# Grove_Beginner_Kit_for_Arduino.net
KiCad netlist of a schematic drawn in EAGLE
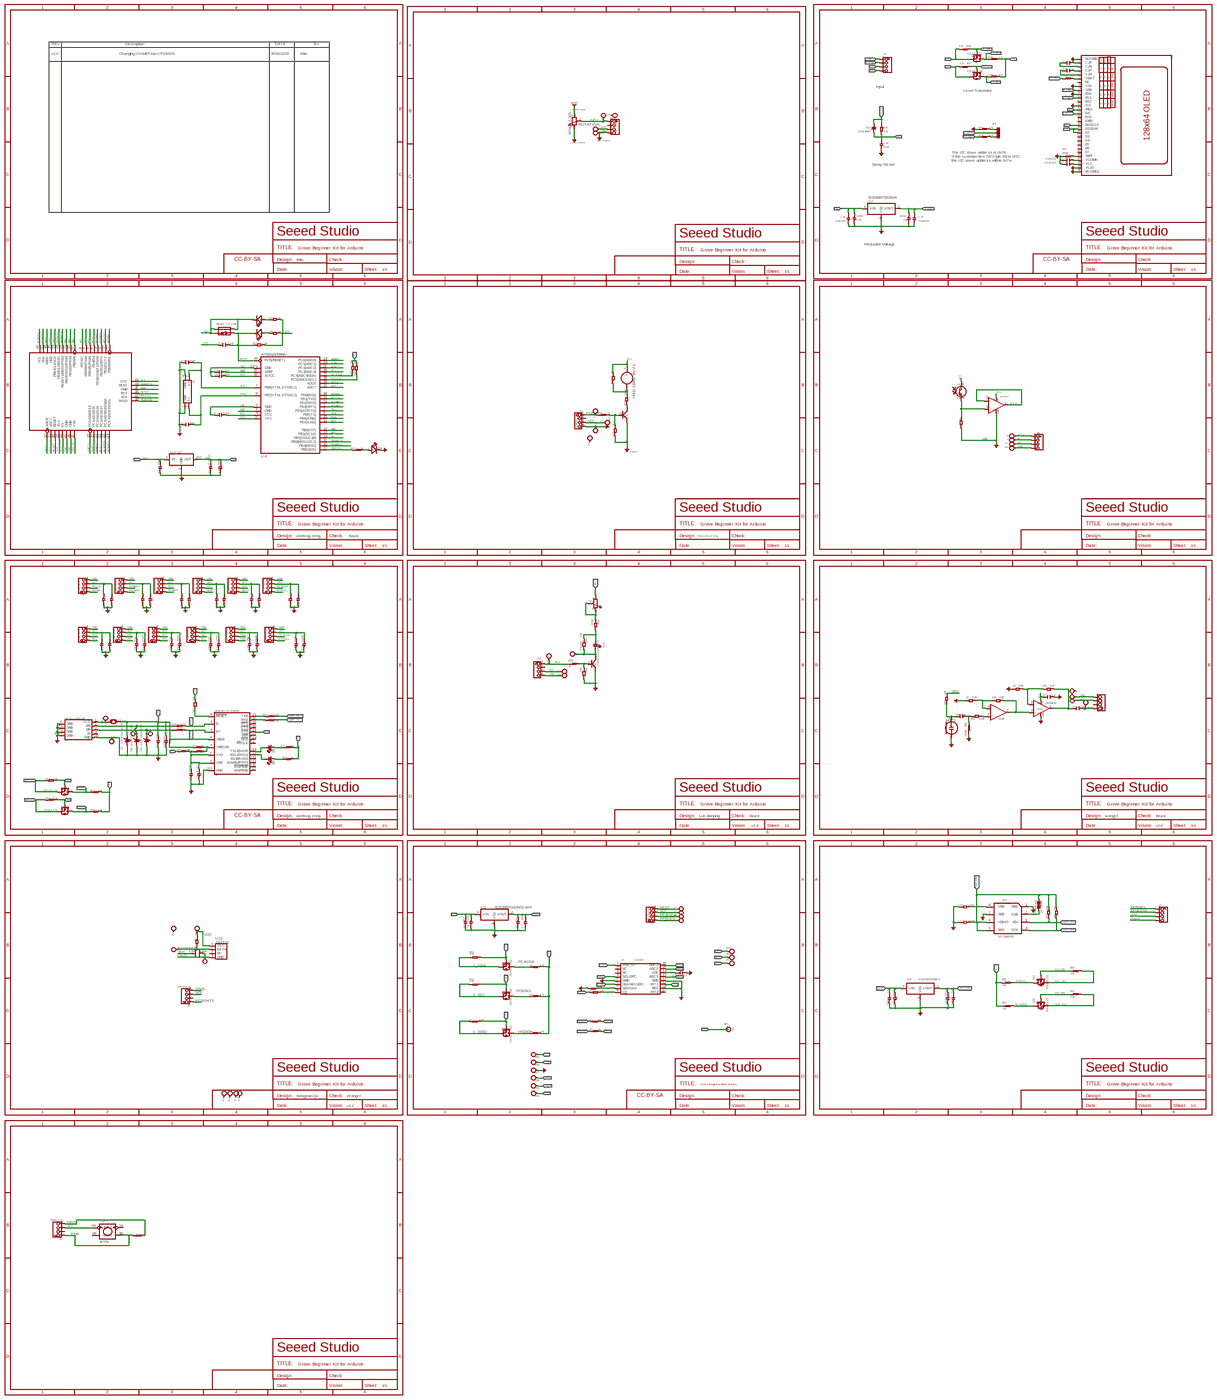
[diagram p0: schematic, sheet 1, overview]
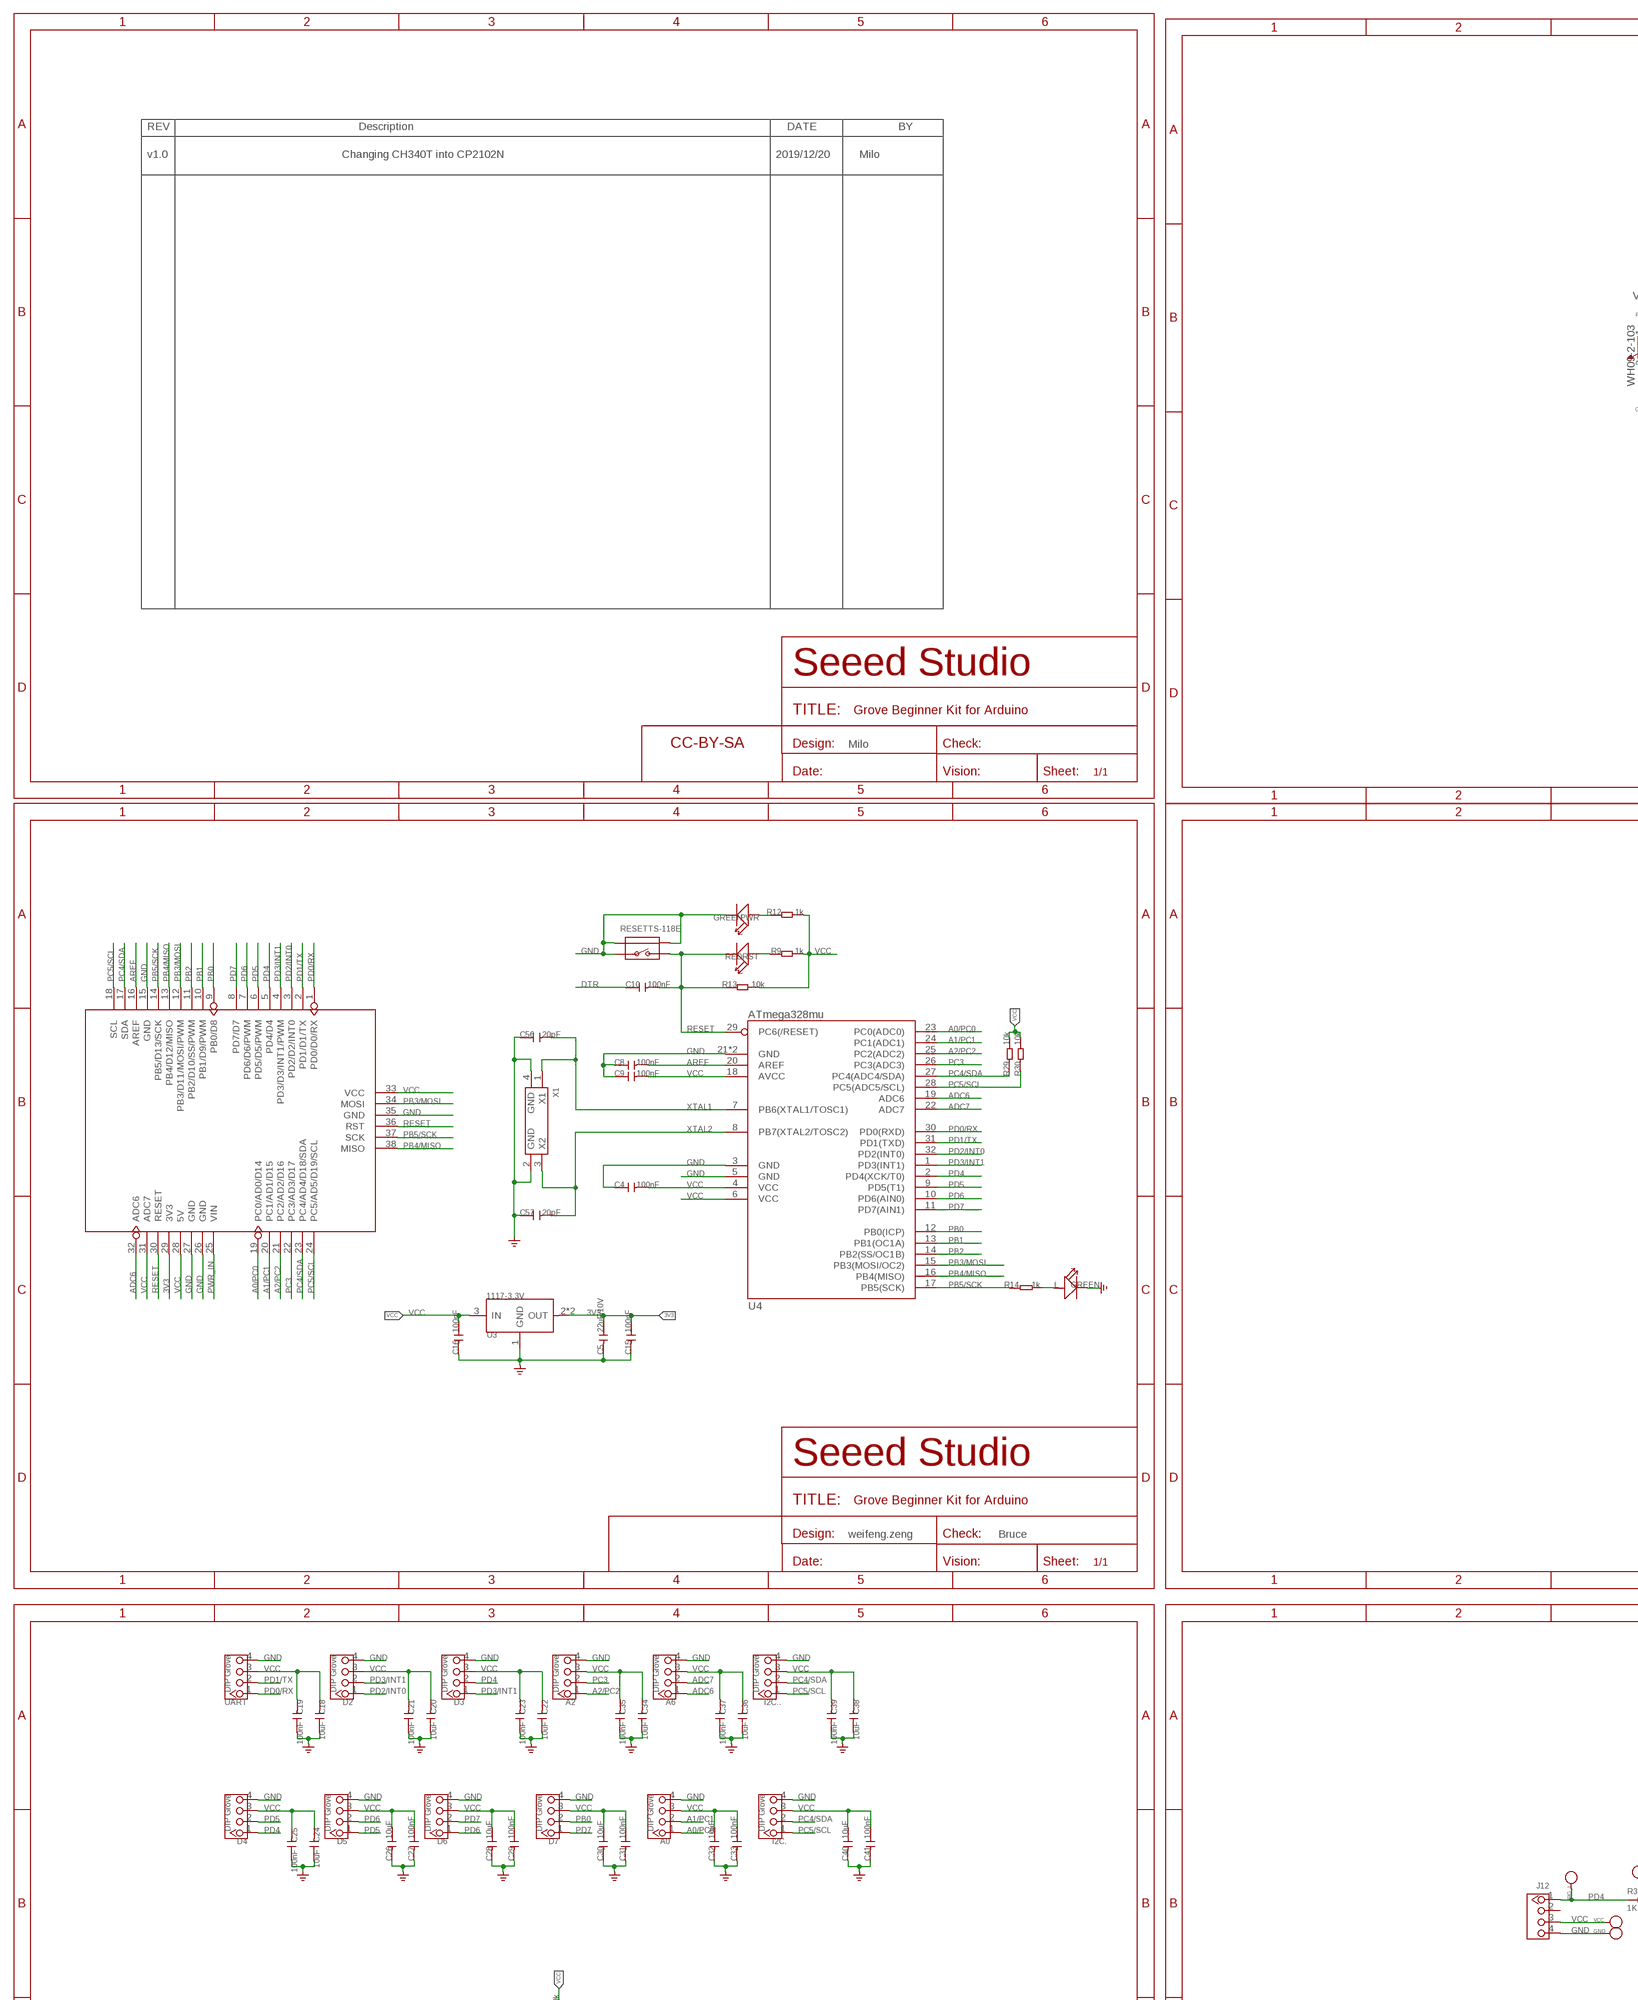
[diagram p1: schematic, sheet 1, part 1 of 4]
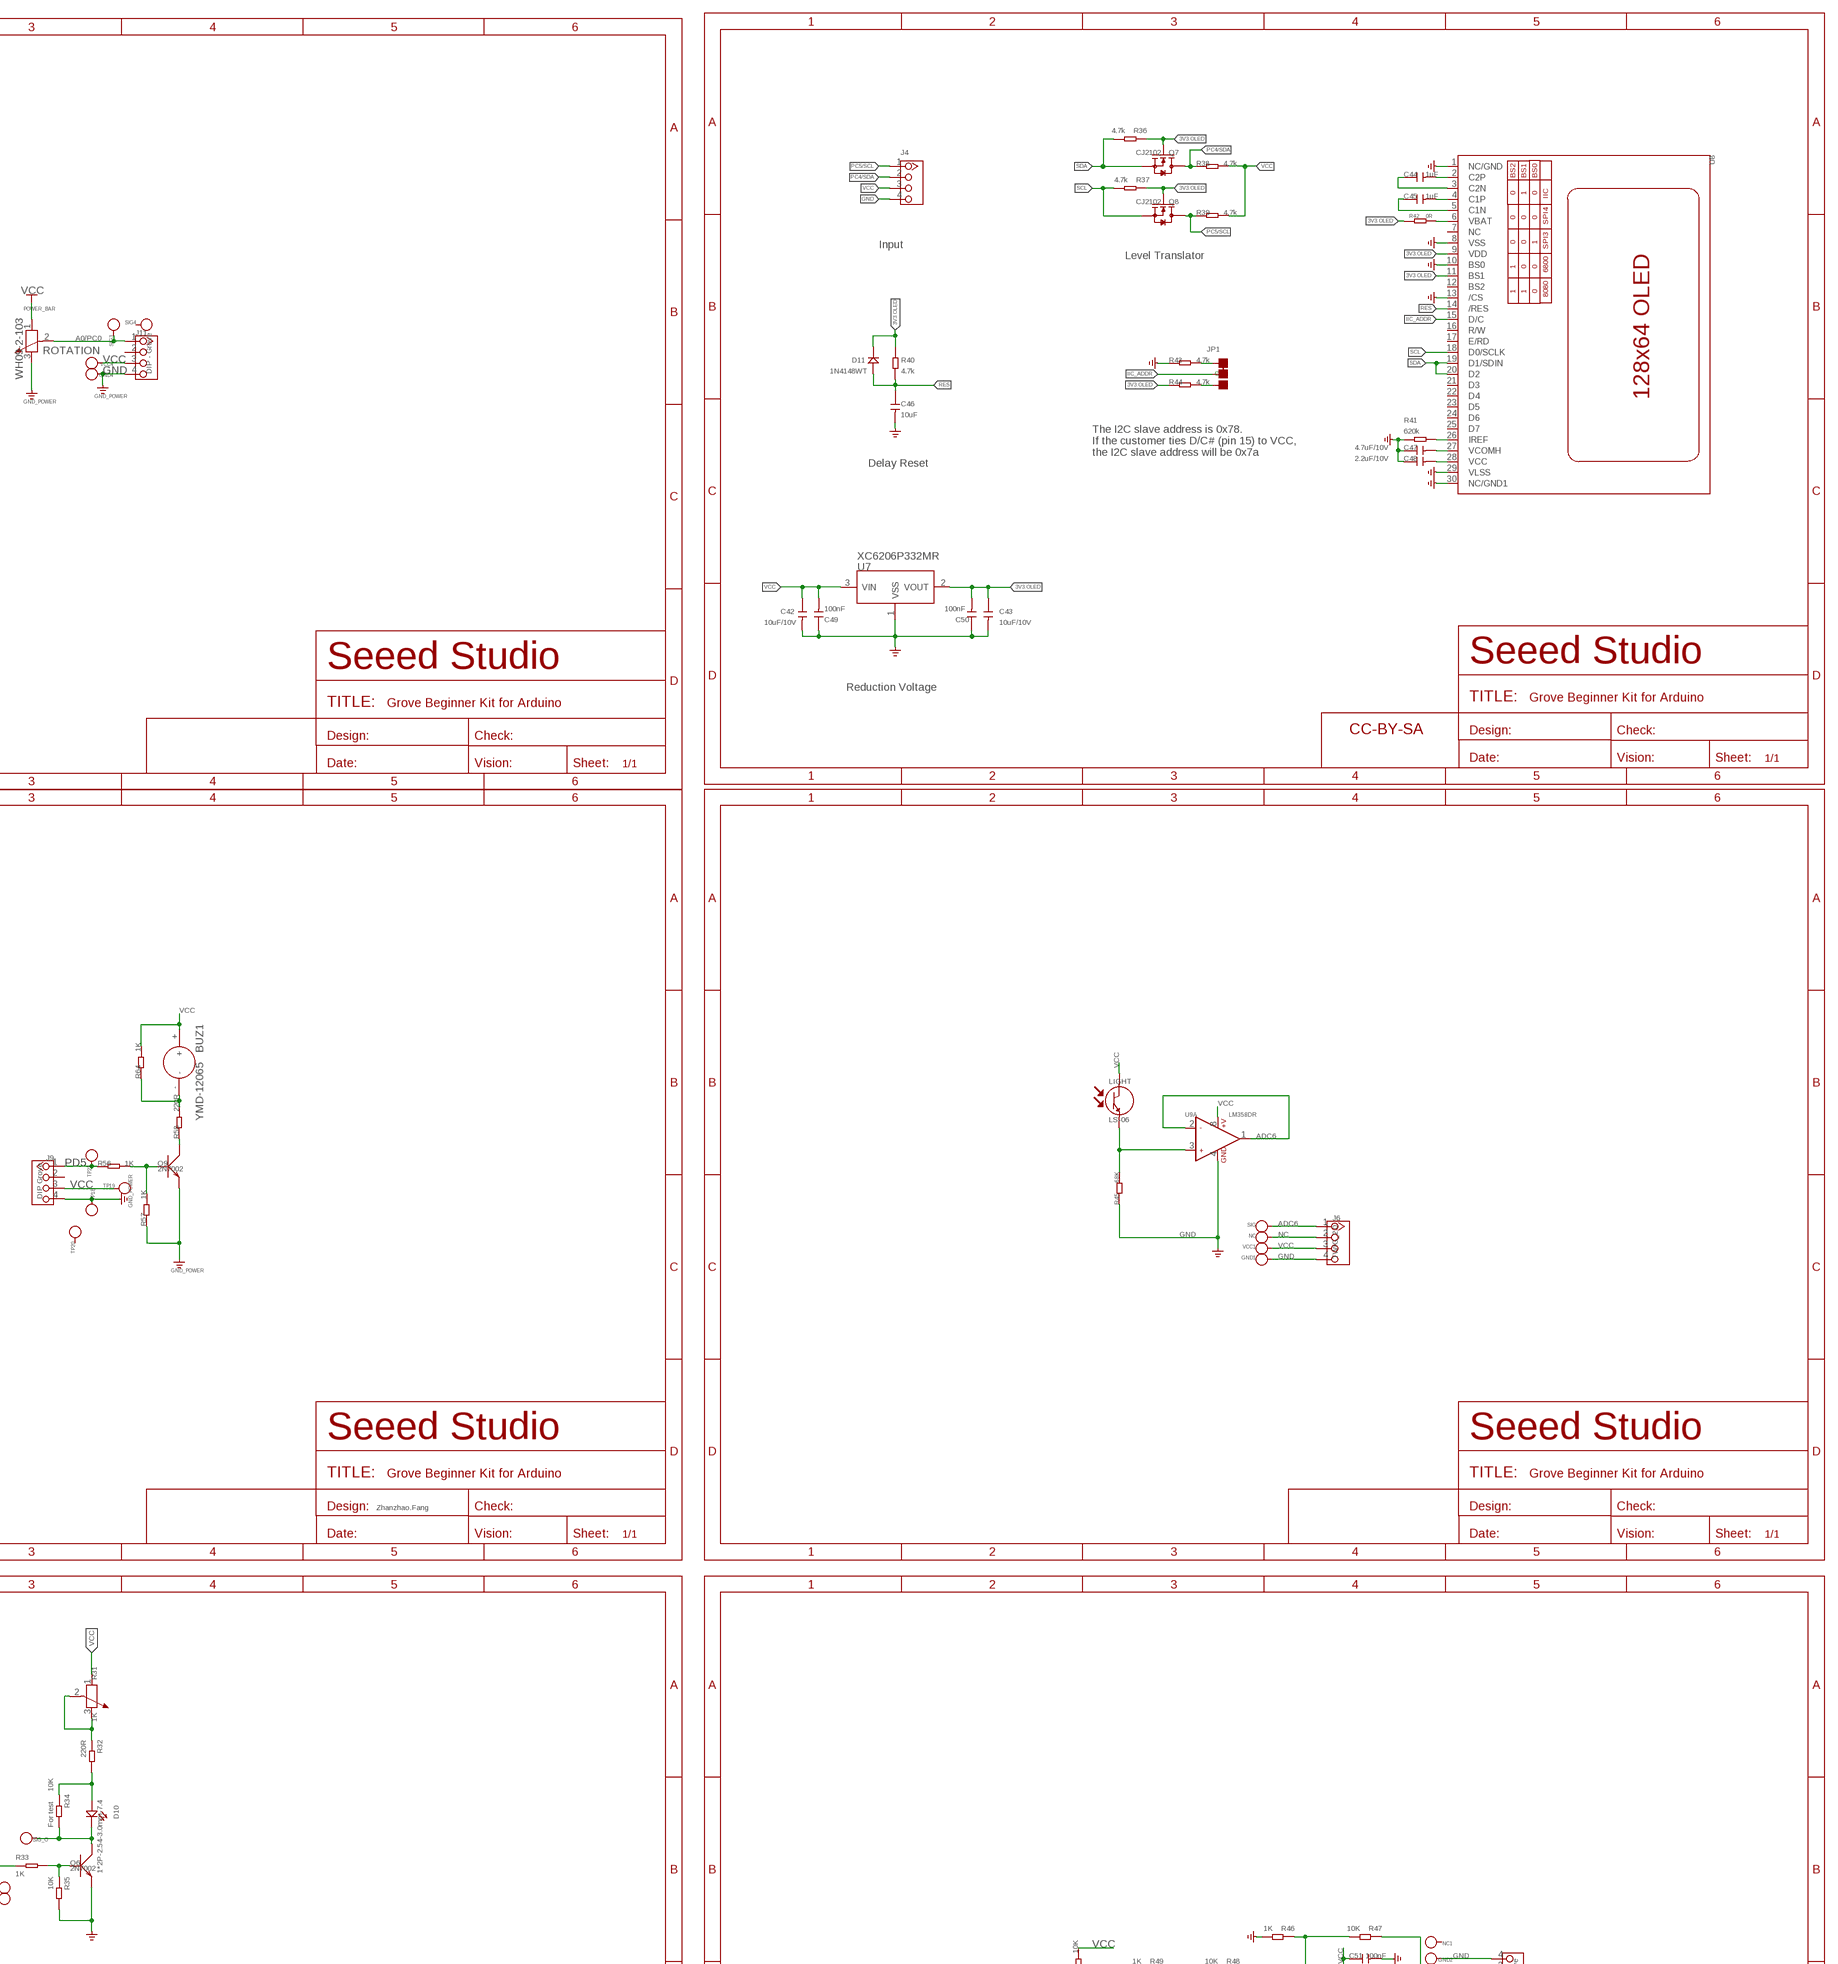
[diagram p2: schematic, sheet 1, part 2 of 4]
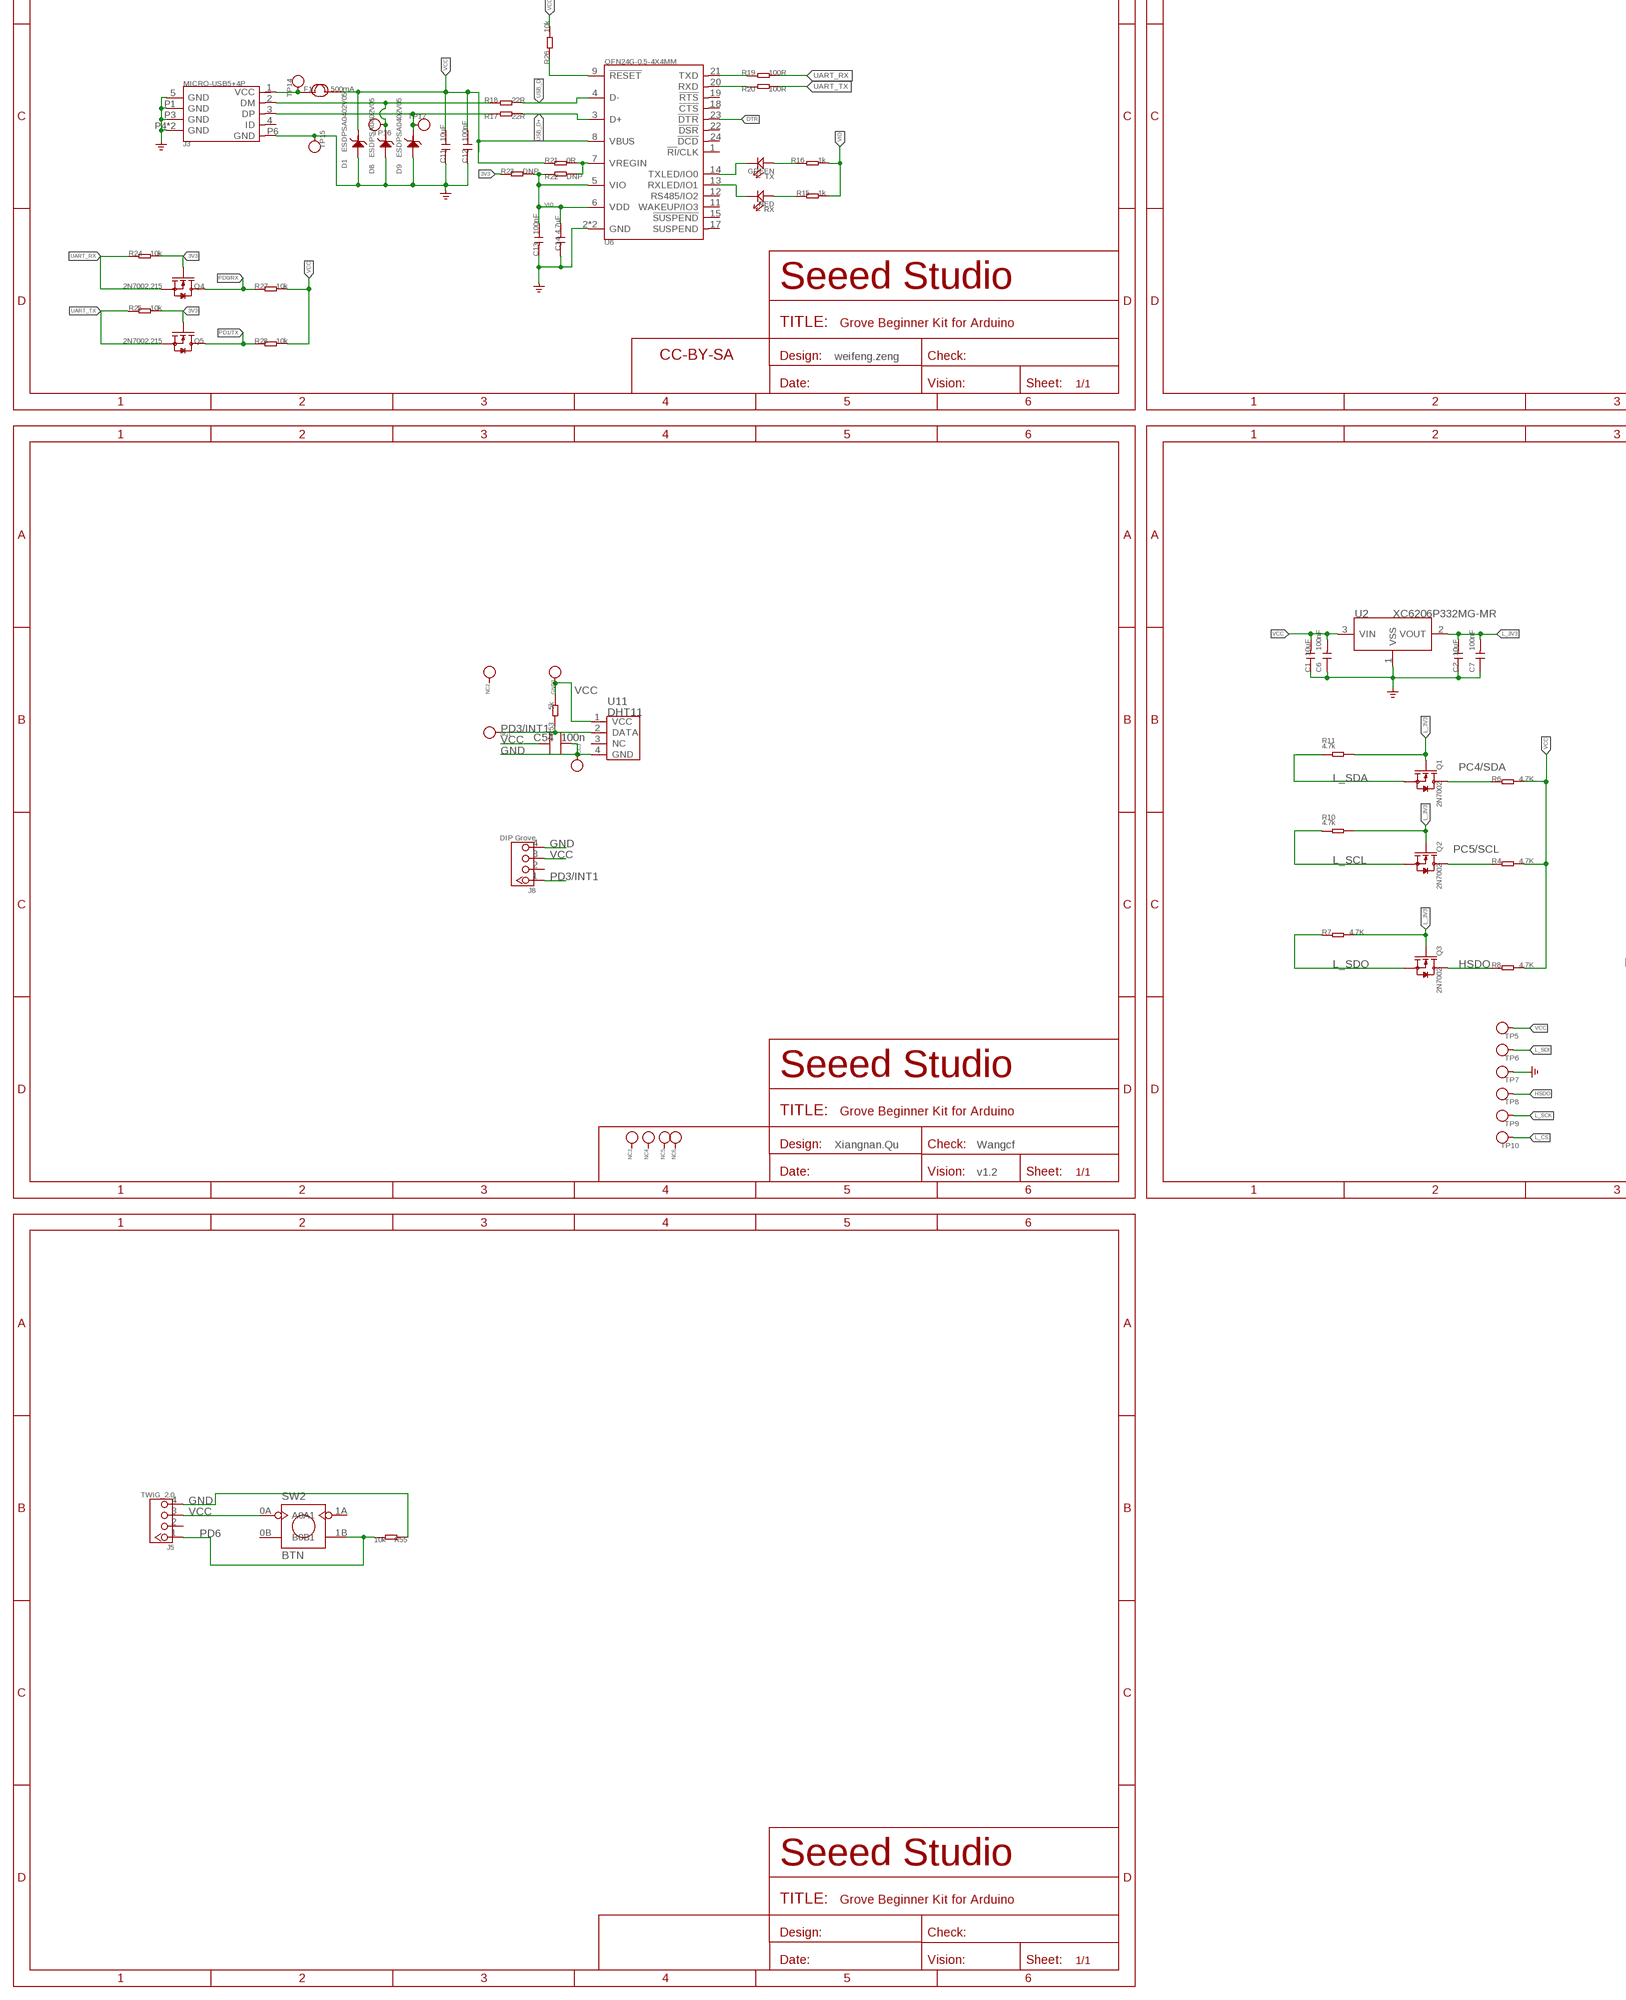
[diagram p3: schematic, sheet 1, part 3 of 4]
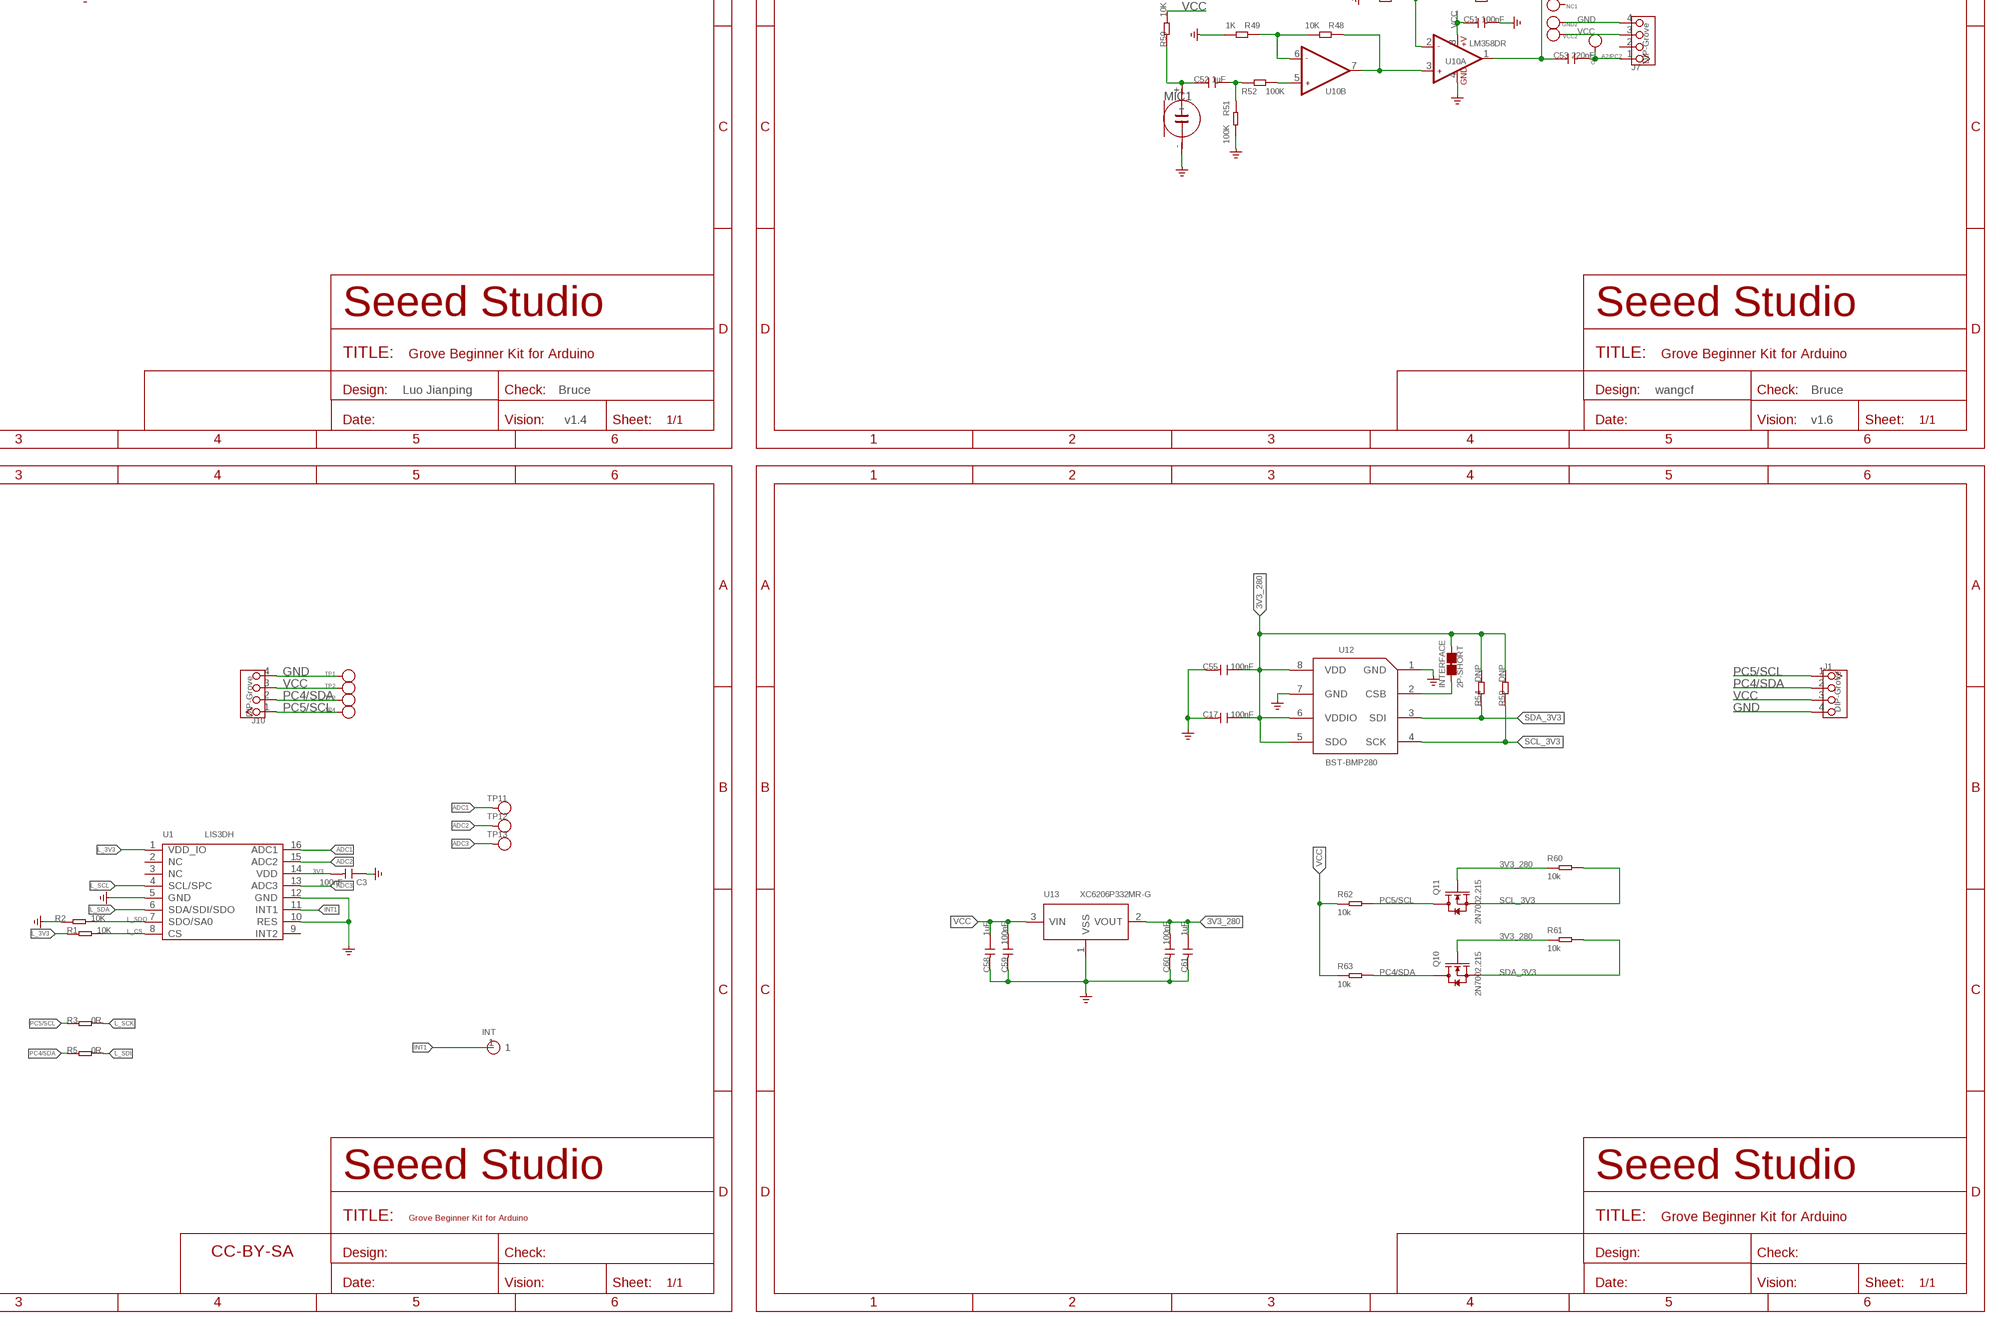
[diagram p4: schematic, sheet 1, part 4 of 4]

(export (version "E")
  (design (tool "Eeschema 10.0.6"))
  (components
    (comp (ref "A0")
      (value "DIP Grove")
      (footprint "eagle-import:4P-2.0")
      (libsource (lib "eagle-import") (part "Connector _TWIG-4P-2.0-2.0"))
    )
    (comp (ref "A2")
      (value "DIP Grove")
      (footprint "eagle-import:4P-2.0")
      (libsource (lib "eagle-import") (part "Connector _TWIG-4P-2.0-2.0"))
    )
    (comp (ref "A6")
      (value "DIP Grove")
      (footprint "eagle-import:4P-2.0")
      (libsource (lib "eagle-import") (part "Connector _TWIG-4P-2.0-2.0"))
    )
    (comp (ref "BUZ1")
      (value "YMD-12065")
      (footprint "eagle-import:2P-7.6-D12X6.5H")
      (libsource (lib "eagle-import") (part "BUZZER-YMD12065"))
    )
    (comp (ref "C1")
      (value "10uF")
      (footprint "eagle-import:C0603")
      (libsource (lib "eagle-import") (part "discrete_C-0603"))
    )
    (comp (ref "C2")
      (value "10uF")
      (footprint "eagle-import:C0603")
      (libsource (lib "eagle-import") (part "discrete_C-0603"))
    )
    (comp (ref "C3")
      (value "100nF")
      (footprint "eagle-import:C0402")
      (libsource (lib "eagle-import") (part "Discrete-new_CAP-0402"))
    )
    (comp (ref "C4")
      (value "100nF")
      (footprint "eagle-import:C0603")
      (libsource (lib "eagle-import") (part "CAP-0603"))
    )
    (comp (ref "C5")
      (value "22uF/10V")
      (footprint "eagle-import:C0603")
      (libsource (lib "eagle-import") (part "Discrete-new_CAP-0603"))
    )
    (comp (ref "C6")
      (value "100nF")
      (footprint "eagle-import:C0603")
      (libsource (lib "eagle-import") (part "Discrete-new_CAP-0603"))
    )
    (comp (ref "C7")
      (value "100nF")
      (footprint "eagle-import:C0603")
      (libsource (lib "eagle-import") (part "Discrete-new_CAP-0603"))
    )
    (comp (ref "C8")
      (value "100nF")
      (footprint "eagle-import:C0603")
      (libsource (lib "eagle-import") (part "CAP-0603"))
    )
    (comp (ref "C9")
      (value "100nF")
      (footprint "eagle-import:C0603")
      (libsource (lib "eagle-import") (part "CAP-0603"))
    )
    (comp (ref "C10")
      (value "100nF")
      (footprint "eagle-import:C0603")
      (libsource (lib "eagle-import") (part "CAP-0603"))
    )
    (comp (ref "C11")
      (value "10uF")
      (footprint "eagle-import:C0603")
      (libsource (lib "eagle-import") (part "Discrete-new_CAP-0603"))
    )
    (comp (ref "C12")
      (value "100nF")
      (footprint "eagle-import:C0603")
      (libsource (lib "eagle-import") (part "Discrete-new_CAP-0603"))
    )
    (comp (ref "C13")
      (value "100nF")
      (footprint "eagle-import:C0603")
      (libsource (lib "eagle-import") (part "Discrete-new_CAP-0603"))
    )
    (comp (ref "C14")
      (value "4.7uF")
      (footprint "eagle-import:C0603")
      (libsource (lib "eagle-import") (part "Discrete-new_CAP-0603"))
    )
    (comp (ref "C15")
      (value "100nF")
      (footprint "eagle-import:C0603")
      (libsource (lib "eagle-import") (part "Discrete-new_CAP-0603"))
    )
    (comp (ref "C16")
      (value "100nF")
      (footprint "eagle-import:C0603")
      (libsource (lib "eagle-import") (part "Discrete-new_CAP-0603"))
    )
    (comp (ref "C17")
      (value "100nF")
      (footprint "eagle-import:C0603")
      (libsource (lib "eagle-import") (part "Discrete-new_CAP-0603"))
    )
    (comp (ref "C18")
      (value "10uF")
      (footprint "eagle-import:C0603")
      (libsource (lib "eagle-import") (part "Discrete-new_CAP-0603"))
    )
    (comp (ref "C19")
      (value "100nF")
      (footprint "eagle-import:C0603")
      (libsource (lib "eagle-import") (part "Discrete-new_CAP-0603"))
    )
    (comp (ref "C20")
      (value "10uF")
      (footprint "eagle-import:C0603")
      (libsource (lib "eagle-import") (part "Discrete-new_CAP-0603"))
    )
    (comp (ref "C21")
      (value "100nF")
      (footprint "eagle-import:C0603")
      (libsource (lib "eagle-import") (part "Discrete-new_CAP-0603"))
    )
    (comp (ref "C22")
      (value "10uF")
      (footprint "eagle-import:C0603")
      (libsource (lib "eagle-import") (part "Discrete-new_CAP-0603"))
    )
    (comp (ref "C23")
      (value "100nF")
      (footprint "eagle-import:C0603")
      (libsource (lib "eagle-import") (part "Discrete-new_CAP-0603"))
    )
    (comp (ref "C24")
      (value "10uF")
      (footprint "eagle-import:C0603")
      (libsource (lib "eagle-import") (part "Discrete-new_CAP-0603"))
    )
    (comp (ref "C25")
      (value "100nF")
      (footprint "eagle-import:C0603")
      (libsource (lib "eagle-import") (part "Discrete-new_CAP-0603"))
    )
    (comp (ref "C26")
      (value "10uF")
      (footprint "eagle-import:C0603")
      (libsource (lib "eagle-import") (part "Discrete-new_CAP-0603"))
    )
    (comp (ref "C27")
      (value "100nF")
      (footprint "eagle-import:C0603")
      (libsource (lib "eagle-import") (part "Discrete-new_CAP-0603"))
    )
    (comp (ref "C28")
      (value "10uF")
      (footprint "eagle-import:C0603")
      (libsource (lib "eagle-import") (part "Discrete-new_CAP-0603"))
    )
    (comp (ref "C29")
      (value "100nF")
      (footprint "eagle-import:C0603")
      (libsource (lib "eagle-import") (part "Discrete-new_CAP-0603"))
    )
    (comp (ref "C30")
      (value "10uF")
      (footprint "eagle-import:C0603")
      (libsource (lib "eagle-import") (part "Discrete-new_CAP-0603"))
    )
    (comp (ref "C31")
      (value "100nF")
      (footprint "eagle-import:C0603")
      (libsource (lib "eagle-import") (part "Discrete-new_CAP-0603"))
    )
    (comp (ref "C32")
      (value "10uF")
      (footprint "eagle-import:C0603")
      (libsource (lib "eagle-import") (part "Discrete-new_CAP-0603"))
    )
    (comp (ref "C33")
      (value "100nF")
      (footprint "eagle-import:C0603")
      (libsource (lib "eagle-import") (part "Discrete-new_CAP-0603"))
    )
    (comp (ref "C34")
      (value "10uF")
      (footprint "eagle-import:C0603")
      (libsource (lib "eagle-import") (part "Discrete-new_CAP-0603"))
    )
    (comp (ref "C35")
      (value "100nF")
      (footprint "eagle-import:C0603")
      (libsource (lib "eagle-import") (part "Discrete-new_CAP-0603"))
    )
    (comp (ref "C36")
      (value "10uF")
      (footprint "eagle-import:C0603")
      (libsource (lib "eagle-import") (part "Discrete-new_CAP-0603"))
    )
    (comp (ref "C37")
      (value "100nF")
      (footprint "eagle-import:C0603")
      (libsource (lib "eagle-import") (part "Discrete-new_CAP-0603"))
    )
    (comp (ref "C38")
      (value "10uF")
      (footprint "eagle-import:C0603")
      (libsource (lib "eagle-import") (part "Discrete-new_CAP-0603"))
    )
    (comp (ref "C39")
      (value "100nF")
      (footprint "eagle-import:C0603")
      (libsource (lib "eagle-import") (part "Discrete-new_CAP-0603"))
    )
    (comp (ref "C40")
      (value "10uF")
      (footprint "eagle-import:C0603")
      (libsource (lib "eagle-import") (part "Discrete-new_CAP-0603"))
    )
    (comp (ref "C41")
      (value "100nF")
      (footprint "eagle-import:C0603")
      (libsource (lib "eagle-import") (part "Discrete-new_CAP-0603"))
    )
    (comp (ref "C42")
      (value "10uF/10V")
      (footprint "eagle-import:C0603")
      (libsource (lib "eagle-import") (part "C-0603"))
    )
    (comp (ref "C43")
      (value "10uF/10V")
      (footprint "eagle-import:C0603")
      (libsource (lib "eagle-import") (part "C-0603"))
    )
    (comp (ref "C44")
      (value "1uF")
      (footprint "eagle-import:C0402")
      (libsource (lib "eagle-import") (part "C-0402"))
    )
    (comp (ref "C45")
      (value "1uF")
      (footprint "eagle-import:C0402")
      (libsource (lib "eagle-import") (part "C-0402"))
    )
    (comp (ref "C46")
      (value "10uF")
      (footprint "eagle-import:C0603")
      (libsource (lib "eagle-import") (part "C-0603"))
    )
    (comp (ref "C47")
      (value "4.7uF/10V")
      (footprint "eagle-import:C0603")
      (libsource (lib "eagle-import") (part "C-0603"))
    )
    (comp (ref "C48")
      (value "2.2uF/10V")
      (footprint "eagle-import:C0603")
      (libsource (lib "eagle-import") (part "C-0603"))
    )
    (comp (ref "C49")
      (value "100nF")
      (footprint "eagle-import:C0402")
      (libsource (lib "eagle-import") (part "C-0402"))
    )
    (comp (ref "C50")
      (value "100nF")
      (footprint "eagle-import:C0402")
      (libsource (lib "eagle-import") (part "C-0402"))
    )
    (comp (ref "C51")
      (value "100nF")
      (footprint "eagle-import:C0603")
      (libsource (lib "eagle-import") (part "discrete_C-0603"))
    )
    (comp (ref "C52")
      (value "1uF")
      (footprint "eagle-import:C0603")
      (libsource (lib "eagle-import") (part "discrete_C-0603"))
    )
    (comp (ref "C53")
      (value "220nF")
      (footprint "eagle-import:C0603")
      (libsource (lib "eagle-import") (part "discrete_C-0603"))
    )
    (comp (ref "C54")
      (value "100n")
      (footprint "eagle-import:0603")
      (libsource (lib "eagle-import") (part "C0603"))
    )
    (comp (ref "C55")
      (value "100nF")
      (footprint "eagle-import:C0603")
      (libsource (lib "eagle-import") (part "Discrete-new_CAP-0603"))
    )
    (comp (ref "C56")
      (value "20pF")
      (footprint "eagle-import:C0603")
      (libsource (lib "eagle-import") (part "CAP-0603"))
    )
    (comp (ref "C57")
      (value "20pF")
      (footprint "eagle-import:C0603")
      (libsource (lib "eagle-import") (part "CAP-0603"))
    )
    (comp (ref "C58")
      (value "1uF")
      (footprint "eagle-import:C0603")
      (libsource (lib "eagle-import") (part "Discrete-new_CAP-0603"))
    )
    (comp (ref "C59")
      (value "100nF")
      (footprint "eagle-import:C0603")
      (libsource (lib "eagle-import") (part "Discrete-new_CAP-0603"))
    )
    (comp (ref "C60")
      (value "100nF")
      (footprint "eagle-import:C0603")
      (libsource (lib "eagle-import") (part "Discrete-new_CAP-0603"))
    )
    (comp (ref "C61")
      (value "1uF")
      (footprint "eagle-import:C0603")
      (libsource (lib "eagle-import") (part "Discrete-new_CAP-0603"))
    )
    (comp (ref "D1")
      (value "ESDPSA0402V05")
      (footprint "eagle-import:SOD-923")
      (libsource (lib "eagle-import") (part "D-ESD-2P'DF2S6.8FS'"))
    )
    (comp (ref "D2")
      (value "DIP Grove")
      (footprint "eagle-import:4P-2.0")
      (libsource (lib "eagle-import") (part "TWIG-4P-2.0-2.0"))
    )
    (comp (ref "D3")
      (value "DIP Grove")
      (footprint "eagle-import:4P-2.0")
      (libsource (lib "eagle-import") (part "TWIG-4P-2.0-2.0"))
    )
    (comp (ref "D4")
      (value "DIP Grove")
      (footprint "eagle-import:4P-2.0")
      (libsource (lib "eagle-import") (part "TWIG-4P-2.0-2.0"))
    )
    (comp (ref "D5")
      (value "DIP Grove")
      (footprint "eagle-import:4P-2.0")
      (libsource (lib "eagle-import") (part "TWIG-4P-2.0-2.0"))
    )
    (comp (ref "D6")
      (value "DIP Grove")
      (footprint "eagle-import:4P-2.0")
      (libsource (lib "eagle-import") (part "TWIG-4P-2.0-2.0"))
    )
    (comp (ref "D7")
      (value "DIP Grove")
      (footprint "eagle-import:4P-2.0")
      (libsource (lib "eagle-import") (part "TWIG-4P-2.0-2.0"))
    )
    (comp (ref "D8")
      (value "ESDPSA0402V05")
      (footprint "eagle-import:SOD-923")
      (libsource (lib "eagle-import") (part "D-ESD-2P'DF2S6.8FS'"))
    )
    (comp (ref "D9")
      (value "ESDPSA0402V05")
      (footprint "eagle-import:SOD-923")
      (libsource (lib "eagle-import") (part "D-ESD-2P'DF2S6.8FS'"))
    )
    (comp (ref "D10")
      (value "1*2P-2.54-3.0mm-7.4")
      (footprint "eagle-import:LED-2P-2.54-6MM")
      (libsource (lib "eagle-import") (part "LED-2.54-6MM"))
    )
    (comp (ref "D11")
      (value "1N4148WT")
      (footprint "eagle-import:SOD-523")
      (libsource (lib "eagle-import") (part "DIODE'0603'"))
    )
    (comp (ref "F1")
      (value "500mA")
      (footprint "eagle-import:F1206")
      (libsource (lib "eagle-import") (part "FUSE'1206'"))
    )
    (comp (ref "FR2")
      (value "SEEEDSTUDIO-OPEN-SCH-FRAME")
      (footprint "eagle-import:SEEEDSTUDIO-PCB-FRAME")
      (libsource (lib "eagle-import") (part "SEEEDSTUDIO-OPEN-SCH-FRAME"))
    )
    (comp (ref "FR3")
      (value "SEEEDSTUDIO-OPEN-SCH-FRAME")
      (footprint "eagle-import:SEEEDSTUDIO-PCB-FRAME")
      (libsource (lib "eagle-import") (part "SEEEDSTUDIO-OPEN-SCH-FRAME"))
    )
    (comp (ref "FR4")
      (value "SEEEDSTUDIO-OPEN-SCH-FRAME")
      (footprint "eagle-import:SEEEDSTUDIO-PCB-FRAME")
      (libsource (lib "eagle-import") (part "SEEEDSTUDIO-OPEN-SCH-FRAME"))
    )
    (comp (ref "FR5")
      (value "SEEEDSTUDIO-OPEN-SCH-FRAME")
      (footprint "eagle-import:SEEEDSTUDIO-PCB-FRAME")
      (libsource (lib "eagle-import") (part "SEEEDSTUDIO-OPEN-SCH-FRAME"))
    )
    (comp (ref "GND")
      (value "PAD-TEST-POINT'4545'")
      (footprint "eagle-import:TP_4545")
      (fields (field (name "PARTNO") "DNP"))
      (libsource (lib "eagle-import") (part "PAD-TEST-POINT'4545'"))
    )
    (comp (ref "GND1")
      (value "TEST-POINT'4545'")
      (footprint "eagle-import:TP-D45MIL")
      (fields (field (name "PARTNO") "DNP"))
      (libsource (lib "eagle-import") (part "TEST-POINT'4545'"))
    )
    (comp (ref "GND2")
      (value "PAD-TEST-POINT'4545'")
      (footprint "eagle-import:TP_4545")
      (fields (field (name "PARTNO") "DNP"))
      (libsource (lib "eagle-import") (part "PAD-TEST-POINT'4545'"))
    )
    (comp (ref "GND3")
      (value "PAD-TEST-POINT'4545'")
      (footprint "eagle-import:TP_4545")
      (fields (field (name "PARTNO") "DNP"))
      (libsource (lib "eagle-import") (part "PAD-TEST-POINT'4545'"))
    )
    (comp (ref "GND4")
      (value "PAD-TEST-POINT'4545'")
      (footprint "eagle-import:TP_4545")
      (fields (field (name "PARTNO") "DNP"))
      (libsource (lib "eagle-import") (part "PAD-TEST-POINT'4545'"))
    )
    (comp (ref "I2C.")
      (value "DIP Grove")
      (footprint "eagle-import:4P-2.0")
      (libsource (lib "eagle-import") (part "TWIG-4P-2.0-2.0"))
    )
    (comp (ref "I2C..")
      (value "DIP Grove")
      (footprint "eagle-import:4P-2.0")
      (libsource (lib "eagle-import") (part "TWIG-4P-2.0-2.0"))
    )
    (comp (ref "INT")
      (value "HEADER-1P-35")
      (footprint "eagle-import:1P-65_35MIL")
      (libsource (lib "eagle-import") (part "HEADER-1P-35"))
    )
    (comp (ref "INTERFACE")
      (value "2P-SHORT")
      (footprint "eagle-import:2P-SMD-SHORT")
      (libsource (lib "eagle-import") (part "JUMPER-2P-SHORT"))
    )
    (comp (ref "J1")
      (value "DIP-Grove")
      (footprint "eagle-import:4P-2.0")
      (libsource (lib "eagle-import") (part "Connector _TWIG-4P-2.0-2.0"))
    )
    (comp (ref "J3")
      (value "MICRO-USB5+4P")
      (footprint "eagle-import:MICRO-USB5+5P-SMD-0.65-7.2X5.06MM")
      (libsource (lib "eagle-import") (part "MICRO-USB5+4P"))
    )
    (comp (ref "J4")
      (value "GROVE-CONNECTOR-DIP-320110033")
      (footprint "eagle-import:HW4-2.0")
      (libsource (lib "eagle-import") (part "GROVE-CONNECTOR-DIP-320110033"))
    )
    (comp (ref "J5")
      (value "TWIG_2.0")
      (footprint "eagle-import:2.0_1X4")
      (libsource (lib "eagle-import") (part "TWIG_2.0"))
    )
    (comp (ref "J6")
      (value "TWIG_2.0")
      (footprint "eagle-import:HW4-2.0")
      (libsource (lib "eagle-import") (part "GROVE-CONNECTOR-DIP-320110033"))
    )
    (comp (ref "J7")
      (value "DIP-Grove")
      (footprint "eagle-import:4P-2.0")
      (libsource (lib "eagle-import") (part "Connector _TWIG-4P-2.0-2.0"))
    )
    (comp (ref "J8")
      (value "DIP Grove")
      (footprint "eagle-import:2.0_1X4")
      (libsource (lib "eagle-import") (part "TWIG_2.0"))
    )
    (comp (ref "J9")
      (value "DIP Grove")
      (footprint "eagle-import:4P-2.0")
      (libsource (lib "eagle-import") (part "TWIG-4P-2.0-2.0"))
    )
    (comp (ref "J10")
      (value "DIP-Grove")
      (footprint "eagle-import:4P-2.0")
      (libsource (lib "eagle-import") (part "Connector _TWIG-4P-2.0-2.0"))
    )
    (comp (ref "J11")
      (value "DIP - Grove")
      (footprint "eagle-import:4P-2.0")
      (libsource (lib "eagle-import") (part "Connector _TWIG-4P-2.0-2.0"))
    )
    (comp (ref "J12")
      (value "GROVE-CONNECTOR-DIP-320110033")
      (footprint "eagle-import:HW4-2.0")
      (libsource (lib "eagle-import") (part "GROVE-CONNECTOR-DIP-320110033"))
    )
    (comp (ref "JP1")
      (value "JP-3P-SHORT")
      (footprint "eagle-import:3P-SMD-SHORT@1")
      (libsource (lib "eagle-import") (part "JP-3P-SHORT"))
    )
    (comp (ref "L")
      (value "GREEN")
      (footprint "eagle-import:LED-0603")
      (libsource (lib "eagle-import") (part "discrete_LED'0603'"))
    )
    (comp (ref "LIGHT")
      (value "LS-06")
      (footprint "eagle-import:DIP2P-D5MM-2.54")
      (libsource (lib "eagle-import") (part "PHOTISTOR-PT550"))
    )
    (comp (ref "MIC1")
      (value "MICROPHONE'KS-9745P,-56DB'")
      (footprint "eagle-import:2P-D9.7_4.5H")
      (libsource (lib "eagle-import") (part "MICROPHONE'KS-9745P,-56DB'"))
    )
    (comp (ref "NC")
      (value "TEST-POINT'4545'")
      (footprint "eagle-import:TP-D45MIL")
      (fields (field (name "PARTNO") "DNP"))
      (libsource (lib "eagle-import") (part "TEST-POINT'4545'"))
    )
    (comp (ref "NC1")
      (value "PAD-TEST-POINT'4545'")
      (footprint "eagle-import:TP_4545")
      (fields (field (name "PARTNO") "DNP"))
      (libsource (lib "eagle-import") (part "PAD-TEST-POINT'4545'"))
    )
    (comp (ref "NC2")
      (value "PAD-TEST-POINT'4545'")
      (footprint "eagle-import:TP_4545")
      (fields (field (name "PARTNO") "DNP"))
      (libsource (lib "eagle-import") (part "PAD-TEST-POINT'4545'"))
    )
    (comp (ref "NC3")
      (value "PAD-TEST-POINT'4545'")
      (footprint "eagle-import:TP_4545")
      (fields (field (name "PARTNO") "DNP"))
      (libsource (lib "eagle-import") (part "PAD-TEST-POINT'4545'"))
    )
    (comp (ref "NC4")
      (value "PAD-TEST-POINT'4545'")
      (footprint "eagle-import:TP_4545")
      (fields (field (name "PARTNO") "DNP"))
      (libsource (lib "eagle-import") (part "PAD-TEST-POINT'4545'"))
    )
    (comp (ref "NC5")
      (value "PAD-TEST-POINT'4545'")
      (footprint "eagle-import:TP_4545")
      (fields (field (name "PARTNO") "DNP"))
      (libsource (lib "eagle-import") (part "PAD-TEST-POINT'4545'"))
    )
    (comp (ref "NC6")
      (value "PAD-TEST-POINT'4545'")
      (footprint "eagle-import:TP_4545")
      (fields (field (name "PARTNO") "DNP"))
      (libsource (lib "eagle-import") (part "PAD-TEST-POINT'4545'"))
    )
    (comp (ref "OUT")
      (value "PAD-TEST-POINT'4545'")
      (footprint "eagle-import:TP_4545")
      (fields (field (name "PARTNO") "DNP"))
      (libsource (lib "eagle-import") (part "PAD-TEST-POINT'4545'"))
    )
    (comp (ref "PWR")
      (value "GREEN")
      (footprint "eagle-import:LED-0603")
      (libsource (lib "eagle-import") (part "discrete_LED'0603'"))
    )
    (comp (ref "Q1")
      (value "2N7002")
      (footprint "eagle-import:SOT23")
      (libsource (lib "eagle-import") (part "discrete_MOSFET-N'SOT23'"))
    )
    (comp (ref "Q2")
      (value "2N7002")
      (footprint "eagle-import:SOT23")
      (libsource (lib "eagle-import") (part "discrete_MOSFET-N'SOT23'"))
    )
    (comp (ref "Q3")
      (value "2N7002")
      (footprint "eagle-import:SOT23")
      (libsource (lib "eagle-import") (part "discrete_MOSFET-N'SOT23'"))
    )
    (comp (ref "Q4")
      (value "2N7002,215")
      (footprint "eagle-import:SOT-23")
      (libsource (lib "eagle-import") (part "MOSFET-N'SOT23'"))
    )
    (comp (ref "Q5")
      (value "2N7002,215")
      (footprint "eagle-import:SOT-23")
      (libsource (lib "eagle-import") (part "MOSFET-N'SOT23'"))
    )
    (comp (ref "Q6")
      (value "2N7002")
      (footprint "eagle-import:SOT23")
      (libsource (lib "eagle-import") (part "TRANSISTOR-NPN-SOT23"))
    )
    (comp (ref "Q7")
      (value "CJ2102")
      (footprint "eagle-import:SOT-323")
      (libsource (lib "eagle-import") (part "MOSFET-N'SI1304BDL'"))
    )
    (comp (ref "Q8")
      (value "CJ2102")
      (footprint "eagle-import:SOT-323")
      (libsource (lib "eagle-import") (part "MOSFET-N'SI1304BDL'"))
    )
    (comp (ref "Q9")
      (value "2N7002")
      (footprint "eagle-import:SOT23")
      (libsource (lib "eagle-import") (part "TRANSISTOR-NPN-SOT23"))
    )
    (comp (ref "Q10")
      (value "2N7002,215")
      (footprint "eagle-import:SOT-23")
      (libsource (lib "eagle-import") (part "MOSFET-N'SOT23'"))
    )
    (comp (ref "Q11")
      (value "2N7002,215")
      (footprint "eagle-import:SOT-23")
      (libsource (lib "eagle-import") (part "MOSFET-N'SOT23'"))
    )
    (comp (ref "R1")
      (value "10K")
      (footprint "eagle-import:R0402")
      (libsource (lib "eagle-import") (part "Discrete-new_RES-0402"))
    )
    (comp (ref "R2")
      (value "10K")
      (footprint "eagle-import:R0402")
      (libsource (lib "eagle-import") (part "Discrete-new_RES-0402"))
    )
    (comp (ref "R3")
      (value "0R")
      (footprint "eagle-import:R0402")
      (libsource (lib "eagle-import") (part "Discrete-new_RES-0402"))
    )
    (comp (ref "R4")
      (value "4.7K")
      (footprint "eagle-import:R0402")
      (libsource (lib "eagle-import") (part "discrete_R-0402"))
    )
    (comp (ref "R5")
      (value "0R")
      (footprint "eagle-import:R0402")
      (libsource (lib "eagle-import") (part "Discrete-new_RES-0402"))
    )
    (comp (ref "R6")
      (value "4.7K")
      (footprint "eagle-import:R0402")
      (libsource (lib "eagle-import") (part "discrete_R-0402"))
    )
    (comp (ref "R7")
      (value "4.7K")
      (footprint "eagle-import:R0402")
      (libsource (lib "eagle-import") (part "discrete_R-0402"))
    )
    (comp (ref "R8")
      (value "4.7K")
      (footprint "eagle-import:R0402")
      (libsource (lib "eagle-import") (part "discrete_R-0402"))
    )
    (comp (ref "R9")
      (value "1k")
      (footprint "eagle-import:R0603")
      (libsource (lib "eagle-import") (part "RES-0603"))
    )
    (comp (ref "R10")
      (value "4.7k")
      (footprint "eagle-import:R0402")
      (libsource (lib "eagle-import") (part "Discrete-new_RES-0402"))
    )
    (comp (ref "R11")
      (value "4.7k")
      (footprint "eagle-import:R0402")
      (libsource (lib "eagle-import") (part "Discrete-new_RES-0402"))
    )
    (comp (ref "R12")
      (value "1k")
      (footprint "eagle-import:R0603")
      (libsource (lib "eagle-import") (part "RES-0603"))
    )
    (comp (ref "R13")
      (value "10k")
      (footprint "eagle-import:R0603")
      (libsource (lib "eagle-import") (part "RES-0603"))
    )
    (comp (ref "R14")
      (value "1k")
      (footprint "eagle-import:R0603")
      (libsource (lib "eagle-import") (part "RES-0603"))
    )
    (comp (ref "R15")
      (value "1k")
      (footprint "eagle-import:R0603")
      (libsource (lib "eagle-import") (part "Discrete-new_RES-0603"))
    )
    (comp (ref "R16")
      (value "1k")
      (footprint "eagle-import:R0603")
      (libsource (lib "eagle-import") (part "Discrete-new_RES-0603"))
    )
    (comp (ref "R17")
      (value "22R")
      (footprint "eagle-import:R0603")
      (libsource (lib "eagle-import") (part "Discrete-new_RES-0603"))
    )
    (comp (ref "R18")
      (value "22R")
      (footprint "eagle-import:R0603")
      (libsource (lib "eagle-import") (part "Discrete-new_RES-0603"))
    )
    (comp (ref "R19")
      (value "100R")
      (footprint "eagle-import:R0603")
      (libsource (lib "eagle-import") (part "Discrete-new_RES-0603"))
    )
    (comp (ref "R20")
      (value "100R")
      (footprint "eagle-import:R0603")
      (libsource (lib "eagle-import") (part "Discrete-new_RES-0603"))
    )
    (comp (ref "R21")
      (value "0R")
      (footprint "eagle-import:R0603")
      (libsource (lib "eagle-import") (part "Discrete-new_RES-0603"))
    )
    (comp (ref "R22")
      (value "DNP")
      (footprint "eagle-import:R0603")
      (libsource (lib "eagle-import") (part "Discrete-new_RES-0603"))
    )
    (comp (ref "R23")
      (value "DNP")
      (footprint "eagle-import:R0603")
      (libsource (lib "eagle-import") (part "Discrete-new_RES-0603"))
    )
    (comp (ref "R24")
      (value "10k")
      (footprint "eagle-import:R0603")
      (libsource (lib "eagle-import") (part "Discrete-new_RES-0603"))
    )
    (comp (ref "R25")
      (value "10k")
      (footprint "eagle-import:R0603")
      (libsource (lib "eagle-import") (part "Discrete-new_RES-0603"))
    )
    (comp (ref "R26")
      (value "10k")
      (footprint "eagle-import:R0603")
      (libsource (lib "eagle-import") (part "Discrete-new_RES-0603"))
    )
    (comp (ref "R27")
      (value "10k")
      (footprint "eagle-import:R0603")
      (libsource (lib "eagle-import") (part "Discrete-new_RES-0603"))
    )
    (comp (ref "R28")
      (value "10k")
      (footprint "eagle-import:R0603")
      (libsource (lib "eagle-import") (part "Discrete-new_RES-0603"))
    )
    (comp (ref "R29")
      (value "10k")
      (footprint "eagle-import:R0603")
      (libsource (lib "eagle-import") (part "Discrete-new_RES-0603"))
    )
    (comp (ref "R30")
      (value "10k")
      (footprint "eagle-import:R0603")
      (libsource (lib "eagle-import") (part "Discrete-new_RES-0603"))
    )
    (comp (ref "R31")
      (value "1K")
      (footprint "eagle-import:ADJR3-6.7X6.4MM")
      (libsource (lib "eagle-import") (part "RES-ADJ'EVN-D8A-A03-B'"))
    )
    (comp (ref "R32")
      (value "220R")
      (footprint "eagle-import:R0603")
      (libsource (lib "eagle-import") (part "Discrete-new_RES-0603"))
    )
    (comp (ref "R33")
      (value "1K")
      (footprint "eagle-import:R0603")
      (libsource (lib "eagle-import") (part "Discrete-new_RES-0603"))
    )
    (comp (ref "R34")
      (value "10K")
      (footprint "eagle-import:R0603")
      (libsource (lib "eagle-import") (part "Discrete-new_RES-0603"))
    )
    (comp (ref "R35")
      (value "10K")
      (footprint "eagle-import:R0603")
      (libsource (lib "eagle-import") (part "Discrete-new_RES-0603"))
    )
    (comp (ref "R36")
      (value "4.7k")
      (footprint "eagle-import:R0402")
      (libsource (lib "eagle-import") (part "R-0402"))
    )
    (comp (ref "R37")
      (value "4.7k")
      (footprint "eagle-import:R0402")
      (libsource (lib "eagle-import") (part "R-0402"))
    )
    (comp (ref "R38")
      (value "4.7k")
      (footprint "eagle-import:R0402")
      (libsource (lib "eagle-import") (part "R-0402"))
    )
    (comp (ref "R39")
      (value "4.7k")
      (footprint "eagle-import:R0402")
      (libsource (lib "eagle-import") (part "R-0402"))
    )
    (comp (ref "R40")
      (value "4.7k")
      (footprint "eagle-import:R0402")
      (libsource (lib "eagle-import") (part "R-0402"))
    )
    (comp (ref "R41")
      (value "620k")
      (footprint "eagle-import:R0402")
      (libsource (lib "eagle-import") (part "R-0402"))
    )
    (comp (ref "R42")
      (value "0R")
      (footprint "eagle-import:R0402")
      (libsource (lib "eagle-import") (part "R-0402"))
    )
    (comp (ref "R43")
      (value "4.7k")
      (footprint "eagle-import:R0402")
      (libsource (lib "eagle-import") (part "R-0402"))
    )
    (comp (ref "R44")
      (value "4.7k")
      (footprint "eagle-import:R0402")
      (libsource (lib "eagle-import") (part "R-0402"))
    )
    (comp (ref "R45")
      (value "68K")
      (footprint "eagle-import:R0603")
      (libsource (lib "eagle-import") (part "Discrete-new_RES-0603"))
    )
    (comp (ref "R46")
      (value "1K")
      (footprint "eagle-import:R0603")
      (libsource (lib "eagle-import") (part "discrete_R-0603"))
    )
    (comp (ref "R47")
      (value "10K")
      (footprint "eagle-import:R0603")
      (libsource (lib "eagle-import") (part "discrete_R-0603"))
    )
    (comp (ref "R48")
      (value "10K")
      (footprint "eagle-import:R0603")
      (libsource (lib "eagle-import") (part "discrete_R-0603"))
    )
    (comp (ref "R49")
      (value "1K")
      (footprint "eagle-import:R0603")
      (libsource (lib "eagle-import") (part "discrete_R-0603"))
    )
    (comp (ref "R50")
      (value "10K")
      (footprint "eagle-import:R0603")
      (libsource (lib "eagle-import") (part "discrete_R-0603"))
    )
    (comp (ref "R51")
      (value "100K")
      (footprint "eagle-import:R0603")
      (libsource (lib "eagle-import") (part "discrete_R-0603"))
    )
    (comp (ref "R52")
      (value "100K")
      (footprint "eagle-import:R0603")
      (libsource (lib "eagle-import") (part "discrete_R-0603"))
    )
    (comp (ref "R53")
      (value "5k")
      (footprint "eagle-import:0603")
      (libsource (lib "eagle-import") (part "R0603"))
    )
    (comp (ref "R54")
      (value "DNP")
      (footprint "eagle-import:R0603")
      (libsource (lib "eagle-import") (part "Discrete-new_RES-0603"))
    )
    (comp (ref "R55")
      (value "10k")
      (footprint "eagle-import:0603")
      (libsource (lib "eagle-import") (part "005-R0603"))
    )
    (comp (ref "R56")
      (value "1K")
      (footprint "eagle-import:R0603")
      (libsource (lib "eagle-import") (part "discrete_R-0603"))
    )
    (comp (ref "R57")
      (value "1K")
      (footprint "eagle-import:R0603")
      (libsource (lib "eagle-import") (part "discrete_R-0603"))
    )
    (comp (ref "R58")
      (value "220R")
      (footprint "eagle-import:R0603")
      (libsource (lib "eagle-import") (part "discrete_R-0603"))
    )
    (comp (ref "R59")
      (value "DNP")
      (footprint "eagle-import:R0603")
      (libsource (lib "eagle-import") (part "Discrete-new_RES-0603"))
    )
    (comp (ref "R60")
      (value "10k")
      (footprint "eagle-import:R0603")
      (libsource (lib "eagle-import") (part "Discrete-new_RES-0603"))
    )
    (comp (ref "R61")
      (value "10k")
      (footprint "eagle-import:R0603")
      (libsource (lib "eagle-import") (part "Discrete-new_RES-0603"))
    )
    (comp (ref "R62")
      (value "10k")
      (footprint "eagle-import:R0603")
      (libsource (lib "eagle-import") (part "Discrete-new_RES-0603"))
    )
    (comp (ref "R63")
      (value "10k")
      (footprint "eagle-import:R0603")
      (libsource (lib "eagle-import") (part "Discrete-new_RES-0603"))
    )
    (comp (ref "R64")
      (value "1K")
      (footprint "eagle-import:R0603")
      (libsource (lib "eagle-import") (part "discrete_R-0603"))
    )
    (comp (ref "RESET")
      (value "TS-118E")
      (footprint "eagle-import:4P-SMD-7X3.5X3.5H")
      (libsource (lib "eagle-import") (part "BUTTON-4P-REINFORCE'TS-1188E'"))
    )
    (comp (ref "ROTATION")
      (value "WH09-2-103")
      (footprint "eagle-import:3P-SQUA-11X9.8X12H")
      (libsource (lib "eagle-import") (part "R-POTENTIOMETER'WH09-2'"))
    )
    (comp (ref "RST")
      (value "RED")
      (footprint "eagle-import:LED-0603")
      (libsource (lib "eagle-import") (part "discrete_LED'0603'"))
    )
    (comp (ref "RX")
      (value "RED")
      (footprint "eagle-import:LED-0603")
      (libsource (lib "eagle-import") (part "LED'0603'"))
    )
    (comp (ref "SIG")
      (value "TEST-POINT'4545'")
      (footprint "eagle-import:TP-D45MIL")
      (fields (field (name "PARTNO") "DNP"))
      (libsource (lib "eagle-import") (part "TEST-POINT'4545'"))
    )
    (comp (ref "SIG1")
      (value "PAD-TEST-POINT'4545'")
      (footprint "eagle-import:TP_4545")
      (fields (field (name "PARTNO") "DNP"))
      (libsource (lib "eagle-import") (part "PAD-TEST-POINT'4545'"))
    )
    (comp (ref "SIG3")
      (value "PAD-TEST-POINT'4545'")
      (footprint "eagle-import:TP_4545")
      (fields (field (name "PARTNO") "DNP"))
      (libsource (lib "eagle-import") (part "PAD-TEST-POINT'4545'"))
    )
    (comp (ref "SIG4")
      (value "PAD-TEST-POINT'4545'")
      (footprint "eagle-import:TP_4545")
      (fields (field (name "PARTNO") "DNP"))
      (libsource (lib "eagle-import") (part "PAD-TEST-POINT'4545'"))
    )
    (comp (ref "SIG_I")
      (value "PAD-TEST-POINT'4545'")
      (footprint "eagle-import:TP_4545")
      (fields (field (name "PARTNO") "DNP"))
      (libsource (lib "eagle-import") (part "PAD-TEST-POINT'4545'"))
    )
    (comp (ref "SIG_O")
      (value "PAD-TEST-POINT'4545'")
      (footprint "eagle-import:TP_4545")
      (fields (field (name "PARTNO") "DNP"))
      (libsource (lib "eagle-import") (part "PAD-TEST-POINT'4545'"))
    )
    (comp (ref "SW2")
      (value "BTN")
      (footprint "eagle-import:BTN_8X8")
      (libsource (lib "eagle-import") (part "BTN"))
    )
    (comp (ref "TP1")
      (value "PAD-TEST-POINT'4545'")
      (footprint "eagle-import:TP_4545")
      (fields (field (name "PARTNO") "DNP"))
      (libsource (lib "eagle-import") (part "PAD-TEST-POINT'4545'"))
    )
    (comp (ref "TP2")
      (value "PAD-TEST-POINT'4545'")
      (footprint "eagle-import:TP_4545")
      (fields (field (name "PARTNO") "DNP"))
      (libsource (lib "eagle-import") (part "PAD-TEST-POINT'4545'"))
    )
    (comp (ref "TP3")
      (value "PAD-TEST-POINT'4545'")
      (footprint "eagle-import:TP_4545")
      (fields (field (name "PARTNO") "DNP"))
      (libsource (lib "eagle-import") (part "PAD-TEST-POINT'4545'"))
    )
    (comp (ref "TP4")
      (value "PAD-TEST-POINT'4545'")
      (footprint "eagle-import:TP_4545")
      (fields (field (name "PARTNO") "DNP"))
      (libsource (lib "eagle-import") (part "PAD-TEST-POINT'4545'"))
    )
    (comp (ref "TP5")
      (value "TEST-POINT'4545'")
      (footprint "eagle-import:TP-D45MIL")
      (fields (field (name "PARTNO") "DNP"))
      (libsource (lib "eagle-import") (part "TEST-POINT'4545'"))
    )
    (comp (ref "TP6")
      (value "TEST-POINT'4545'")
      (footprint "eagle-import:TP-D45MIL")
      (fields (field (name "PARTNO") "DNP"))
      (libsource (lib "eagle-import") (part "TEST-POINT'4545'"))
    )
    (comp (ref "TP7")
      (value "TEST-POINT'4545'")
      (footprint "eagle-import:TP-D45MIL")
      (fields (field (name "PARTNO") "DNP"))
      (libsource (lib "eagle-import") (part "TEST-POINT'4545'"))
    )
    (comp (ref "TP8")
      (value "TEST-POINT'4545'")
      (footprint "eagle-import:TP-D45MIL")
      (fields (field (name "PARTNO") "DNP"))
      (libsource (lib "eagle-import") (part "TEST-POINT'4545'"))
    )
    (comp (ref "TP9")
      (value "TEST-POINT'4545'")
      (footprint "eagle-import:TP-D45MIL")
      (fields (field (name "PARTNO") "DNP"))
      (libsource (lib "eagle-import") (part "TEST-POINT'4545'"))
    )
    (comp (ref "TP10")
      (value "TEST-POINT'4545'")
      (footprint "eagle-import:TP-D45MIL")
      (fields (field (name "PARTNO") "DNP"))
      (libsource (lib "eagle-import") (part "TEST-POINT'4545'"))
    )
    (comp (ref "TP11")
      (value "TEST-POINT'4545'")
      (footprint "eagle-import:TP-D45MIL")
      (fields (field (name "PARTNO") "DNP"))
      (libsource (lib "eagle-import") (part "TEST-POINT'4545'"))
    )
    (comp (ref "TP12")
      (value "TEST-POINT'4545'")
      (footprint "eagle-import:TP-D45MIL")
      (fields (field (name "PARTNO") "DNP"))
      (libsource (lib "eagle-import") (part "TEST-POINT'4545'"))
    )
    (comp (ref "TP13")
      (value "TEST-POINT'4545'")
      (footprint "eagle-import:TP-D45MIL")
      (fields (field (name "PARTNO") "DNP"))
      (libsource (lib "eagle-import") (part "TEST-POINT'4545'"))
    )
    (comp (ref "TP14")
      (value "TEST-POINT'4545'")
      (footprint "eagle-import:TP-D45MIL")
      (fields (field (name "PARTNO") "DNP"))
      (libsource (lib "eagle-import") (part "TEST-POINT'4545'"))
    )
    (comp (ref "TP15")
      (value "TEST-POINT'4545'")
      (footprint "eagle-import:TP-D45MIL")
      (fields (field (name "PARTNO") "DNP"))
      (libsource (lib "eagle-import") (part "TEST-POINT'4545'"))
    )
    (comp (ref "TP16")
      (value "TEST-POINT'4545'")
      (footprint "eagle-import:TP-D45MIL")
      (fields (field (name "PARTNO") "DNP"))
      (libsource (lib "eagle-import") (part "TEST-POINT'4545'"))
    )
    (comp (ref "TP17")
      (value "TEST-POINT'4545'")
      (footprint "eagle-import:TP-D45MIL")
      (fields (field (name "PARTNO") "DNP"))
      (libsource (lib "eagle-import") (part "TEST-POINT'4545'"))
    )
    (comp (ref "TP18")
      (value "PAD-TEST-POINT'4545'")
      (footprint "eagle-import:TP_4545")
      (fields (field (name "PARTNO") "DNP"))
      (libsource (lib "eagle-import") (part "PAD-TEST-POINT'4545'"))
    )
    (comp (ref "TP19")
      (value "PAD-TEST-POINT'4545'")
      (footprint "eagle-import:TP_4545")
      (fields (field (name "PARTNO") "DNP"))
      (libsource (lib "eagle-import") (part "PAD-TEST-POINT'4545'"))
    )
    (comp (ref "TP20")
      (value "PAD-TEST-POINT'4545'")
      (footprint "eagle-import:TP_4545")
      (fields (field (name "PARTNO") "DNP"))
      (libsource (lib "eagle-import") (part "PAD-TEST-POINT'4545'"))
    )
    (comp (ref "TP21")
      (value "PAD-TEST-POINT'4545'")
      (footprint "eagle-import:TP_4545")
      (fields (field (name "PARTNO") "DNP"))
      (libsource (lib "eagle-import") (part "PAD-TEST-POINT'4545'"))
    )
    (comp (ref "TX")
      (value "GREEN")
      (footprint "eagle-import:LED-0603")
      (libsource (lib "eagle-import") (part "LED'0603'"))
    )
    (comp (ref "U1")
      (value "LIS3DH")
      (footprint "eagle-import:LGA16-0.5-3X3MM")
      (libsource (lib "eagle-import") (part "SENSOR-MOTION/POSITION-LIS3DH-314080105"))
    )
    (comp (ref "U2")
      (value "XC6206P332MG-MR")
      (footprint "eagle-import:SOT23")
      (libsource (lib "eagle-import") (part "XC6206MR"))
    )
    (comp (ref "U3")
      (value "1117-3.3V")
      (footprint "eagle-import:SOT89")
      (libsource (lib "eagle-import") (part "LD1117'SOT89'"))
    )
    (comp (ref "U4")
      (value "ATmega328mu")
      (footprint "eagle-import:MLF32X-W_HEAT")
      (libsource (lib "eagle-import") (part "ATMEGA8/168/328MLF"))
    )
    (comp (ref "U5")
      (value "ARDUINO-38P")
      (footprint "eagle-import:ARDUINO-38P")
      (libsource (lib "eagle-import") (part "ARDUINO-38P"))
    )
    (comp (ref "U6")
      (value "QFN24G-0.5-4X4MM")
      (footprint "eagle-import:QFN24G-0.5-4X4MM")
      (libsource (lib "eagle-import") (part "CONVERTER-CP2102N(QFN24)"))
    )
    (comp (ref "U7")
      (value "XC6206P332MR")
      (footprint "eagle-import:SOT-23")
      (libsource (lib "eagle-import") (part "PMIC-XC6206PMR"))
    )
    (comp (ref "U8")
      (value "OLED-12864-30P")
      (footprint "eagle-import:OLED30P-0.7-24.74X16.9MM")
      (libsource (lib "eagle-import") (part "OLED-12864-30P"))
    )
    (comp (ref "U9")
      (value "LM358DR")
      (footprint "eagle-import:SOIC8-1.27-5X4MM")
      (libsource (lib "eagle-import") (part "AMPLIFIER-LMV358'D'"))
    )
    (comp (ref "U10")
      (value "LM358DR")
      (footprint "eagle-import:SO08")
      (libsource (lib "eagle-import") (part "LMV358D"))
    )
    (comp (ref "U11")
      (value "DHT11")
      (footprint "eagle-import:DHT11")
      (libsource (lib "eagle-import") (part "SENSOR-DHT11"))
    )
    (comp (ref "U12")
      (value "BST-BMP280")
      (footprint "eagle-import:LGA8-0.65-2X2.5X0.95MM")
      (fields (field (name "MPN") "BMP280"))
      (libsource (lib "eagle-import") (part "SENSOR-BMP280"))
    )
    (comp (ref "U13")
      (value "XC6206P332MR-G")
      (footprint "eagle-import:SOT-23")
      (libsource (lib "eagle-import") (part "PMIC-XC6206PMR"))
    )
    (comp (ref "UART")
      (value "DIP Grove")
      (footprint "eagle-import:4P-2.0")
      (libsource (lib "eagle-import") (part "TWIG-4P-2.0-2.0"))
    )
    (comp (ref "VCC")
      (value "PAD-TEST-POINT'4545'")
      (footprint "eagle-import:TP_4545")
      (fields (field (name "PARTNO") "DNP"))
      (libsource (lib "eagle-import") (part "PAD-TEST-POINT'4545'"))
    )
    (comp (ref "VCC1")
      (value "TEST-POINT'4545'")
      (footprint "eagle-import:TP-D45MIL")
      (fields (field (name "PARTNO") "DNP"))
      (libsource (lib "eagle-import") (part "TEST-POINT'4545'"))
    )
    (comp (ref "VCC2")
      (value "PAD-TEST-POINT'4545'")
      (footprint "eagle-import:TP_4545")
      (fields (field (name "PARTNO") "DNP"))
      (libsource (lib "eagle-import") (part "PAD-TEST-POINT'4545'"))
    )
    (comp (ref "VCC3")
      (value "PAD-TEST-POINT'4545'")
      (footprint "eagle-import:TP_4545")
      (fields (field (name "PARTNO") "DNP"))
      (libsource (lib "eagle-import") (part "PAD-TEST-POINT'4545'"))
    )
    (comp (ref "VCC4")
      (value "PAD-TEST-POINT'4545'")
      (footprint "eagle-import:TP_4545")
      (fields (field (name "PARTNO") "DNP"))
      (libsource (lib "eagle-import") (part "PAD-TEST-POINT'4545'"))
    )
    (comp (ref "X1")
      (value "CRYSTAL-4P-3225")
      (footprint "eagle-import:X4-SMD-3.2X2.5X0.7MM")
      (libsource (lib "eagle-import") (part "CRYSTAL-4P-3225"))
    )
  )
  (nets
    (net (code "1") (name "/A0{slash}PC0") (class "Default")
      (node (ref "A0") (pin "1") (pinfunction "1_1") (pintype "bidirectional"))
      (node (ref "J11") (pin "1") (pinfunction "1_1") (pintype "bidirectional"))
      (node (ref "ROTATION") (pin "2") (pinfunction "3_2") (pintype "passive"))
      (node (ref "SIG3") (pin "T") (pinfunction "T_T") (pintype "bidirectional"))
      (node (ref "U4") (pin "23") (pinfunction "PC0(ADC0)_23") (pintype "bidirectional"))
      (node (ref "U5") (pin "19") (pinfunction "PC0/AD0/D14_19") (pintype "bidirectional"))
    )
    (net (code "2") (name "/A1{slash}PC1") (class "Default")
      (node (ref "A0") (pin "2") (pinfunction "2_2") (pintype "bidirectional"))
      (node (ref "U4") (pin "24") (pinfunction "PC1(ADC1)_24") (pintype "bidirectional"))
      (node (ref "U5") (pin "20") (pinfunction "PC1/AD1/D15_20") (pintype "bidirectional"))
    )
    (net (code "3") (name "/A2{slash}PC2") (class "Default")
      (node (ref "A2") (pin "1") (pinfunction "1_1") (pintype "bidirectional"))
      (node (ref "C53") (pin "2") (pinfunction "2_2") (pintype "passive"))
      (node (ref "J7") (pin "1") (pinfunction "1_1") (pintype "bidirectional"))
      (node (ref "OUT") (pin "T") (pinfunction "T_T") (pintype "bidirectional"))
      (node (ref "U4") (pin "25") (pinfunction "PC2(ADC2)_25") (pintype "bidirectional"))
      (node (ref "U5") (pin "21") (pinfunction "PC2/AD2/D16_21") (pintype "bidirectional"))
    )
    (net (code "4") (name "/ADC6") (class "Default")
      (node (ref "A6") (pin "1") (pinfunction "1_1") (pintype "bidirectional"))
      (node (ref "J6") (pin "1") (pinfunction "1_1") (pintype "bidirectional"))
      (node (ref "SIG") (pin "T") (pinfunction "T_T") (pintype "bidirectional"))
      (node (ref "U4") (pin "19") (pinfunction "ADC6_19") (pintype "bidirectional"))
      (node (ref "U5") (pin "32") (pinfunction "ADC6_32") (pintype "bidirectional"))
      (node (ref "U9") (pin "1") (pinfunction "OUT1_1") (pintype "output"))
      (node (ref "U9") (pin "2") (pinfunction "-IN1_2") (pintype "input"))
    )
    (net (code "5") (name "/ADC7") (class "Default")
      (node (ref "A6") (pin "2") (pinfunction "2_2") (pintype "bidirectional"))
      (node (ref "U4") (pin "22") (pinfunction "ADC7_22") (pintype "bidirectional"))
    )
    (net (code "6") (name "/AREF") (class "Default")
      (node (ref "C8") (pin "2") (pinfunction "2_2") (pintype "passive"))
      (node (ref "U4") (pin "20") (pinfunction "AREF_20") (pintype "bidirectional"))
      (node (ref "U5") (pin "16") (pinfunction "AREF_16") (pintype "bidirectional"))
    )
    (net (code "7") (name "/L_SDO") (class "Default")
      (node (ref "Q3") (pin "2") (pinfunction "S_2") (pintype "passive"))
      (node (ref "R2") (pin "2") (pinfunction "2_2") (pintype "passive"))
      (node (ref "R7") (pin "1") (pinfunction "1_1") (pintype "passive"))
      (node (ref "U1") (pin "7") (pinfunction "SDO/SA0_7") (pintype "bidirectional"))
    )
    (net (code "8") (name "/NC") (class "Default")
      (node (ref "J6") (pin "2") (pinfunction "2_2") (pintype "bidirectional"))
      (node (ref "NC") (pin "T") (pinfunction "T_T") (pintype "bidirectional"))
    )
    (net (code "9") (name "/PB0") (class "Default")
      (node (ref "D7") (pin "2") (pinfunction "2_2") (pintype "bidirectional"))
      (node (ref "U4") (pin "12") (pinfunction "PB0(ICP)_12") (pintype "bidirectional"))
      (node (ref "U5") (pin "9") (pinfunction "PB0/D8_9") (pintype "bidirectional"))
    )
    (net (code "10") (name "/PB1") (class "Default")
      (node (ref "U4") (pin "13") (pinfunction "PB1(OC1A)_13") (pintype "bidirectional"))
      (node (ref "U5") (pin "10") (pinfunction "PB1/D9/PWM_10") (pintype "bidirectional"))
    )
    (net (code "11") (name "/PB2") (class "Default")
      (node (ref "U4") (pin "14") (pinfunction "PB2(SS/OC1B)_14") (pintype "bidirectional"))
      (node (ref "U5") (pin "11") (pinfunction "PB2/D10/SS/PWM_11") (pintype "bidirectional"))
    )
    (net (code "12") (name "/PB3{slash}MOSI") (class "Default")
      (node (ref "U4") (pin "15") (pinfunction "PB3(MOSI/OC2)_15") (pintype "bidirectional"))
      (node (ref "U5") (pin "12") (pinfunction "PB3/D11/MOSI/PWM_12") (pintype "bidirectional"))
      (node (ref "U5") (pin "34") (pinfunction "MOSI_34") (pintype "bidirectional"))
    )
    (net (code "13") (name "/PB4{slash}MISO") (class "Default")
      (node (ref "U4") (pin "16") (pinfunction "PB4(MISO)_16") (pintype "bidirectional"))
      (node (ref "U5") (pin "13") (pinfunction "PB4/D12/MISO_13") (pintype "bidirectional"))
      (node (ref "U5") (pin "38") (pinfunction "MISO_38") (pintype "bidirectional"))
    )
    (net (code "14") (name "/PB5{slash}SCK") (class "Default")
      (node (ref "R14") (pin "1") (pinfunction "1_1") (pintype "passive"))
      (node (ref "U4") (pin "17") (pinfunction "PB5(SCK)_17") (pintype "bidirectional"))
      (node (ref "U5") (pin "14") (pinfunction "PB5/D13/SCK_14") (pintype "bidirectional"))
      (node (ref "U5") (pin "37") (pinfunction "SCK_37") (pintype "bidirectional"))
    )
    (net (code "15") (name "/PC3") (class "Default")
      (node (ref "A2") (pin "2") (pinfunction "2_2") (pintype "bidirectional"))
      (node (ref "U4") (pin "26") (pinfunction "PC3(ADC3)_26") (pintype "bidirectional"))
      (node (ref "U5") (pin "22") (pinfunction "PC3/AD3/D17_22") (pintype "bidirectional"))
    )
    (net (code "16") (name "/PD2{slash}INT0") (class "Default")
      (node (ref "D2") (pin "1") (pinfunction "1_1") (pintype "bidirectional"))
      (node (ref "U4") (pin "32") (pinfunction "PD2(INT0)_32") (pintype "bidirectional"))
      (node (ref "U5") (pin "3") (pinfunction "PD2/D2/INT0_3") (pintype "bidirectional"))
    )
    (net (code "17") (name "/PD3{slash}INT1") (class "Default")
      (node (ref "D2") (pin "2") (pinfunction "2_2") (pintype "bidirectional"))
      (node (ref "D3") (pin "1") (pinfunction "1_1") (pintype "bidirectional"))
      (node (ref "J8") (pin "1") (pinfunction "1_1") (pintype "bidirectional"))
      (node (ref "R53") (pin "1") (pinfunction "1_1") (pintype "bidirectional"))
      (node (ref "SIG1") (pin "T") (pinfunction "T_T") (pintype "bidirectional"))
      (node (ref "U11") (pin "2") (pinfunction "DATA_2") (pintype "bidirectional"))
      (node (ref "U4") (pin "1") (pinfunction "PD3(INT1)_1") (pintype "bidirectional"))
      (node (ref "U5") (pin "4") (pinfunction "PD3/D3/INT1/PWM_4") (pintype "bidirectional"))
    )
    (net (code "18") (name "/PD4") (class "Default")
      (node (ref "D3") (pin "2") (pinfunction "2_2") (pintype "bidirectional"))
      (node (ref "D4") (pin "1") (pinfunction "1_1") (pintype "bidirectional"))
      (node (ref "J12") (pin "1") (pinfunction "1_1") (pintype "bidirectional"))
      (node (ref "R33") (pin "1") (pinfunction "1_1") (pintype "passive"))
      (node (ref "SIG_I") (pin "T") (pinfunction "T_T") (pintype "bidirectional"))
      (node (ref "U4") (pin "2") (pinfunction "PD4(XCK/T0)_2") (pintype "bidirectional"))
      (node (ref "U5") (pin "5") (pinfunction "PD4/D4_5") (pintype "bidirectional"))
    )
    (net (code "19") (name "/PD5") (class "Default")
      (node (ref "D4") (pin "2") (pinfunction "2_2") (pintype "bidirectional"))
      (node (ref "D5") (pin "1") (pinfunction "1_1") (pintype "bidirectional"))
      (node (ref "J9") (pin "1") (pinfunction "1_1") (pintype "bidirectional"))
      (node (ref "R56") (pin "1") (pinfunction "1_1") (pintype "passive"))
      (node (ref "TP21") (pin "T") (pinfunction "T_T") (pintype "bidirectional"))
      (node (ref "U4") (pin "9") (pinfunction "PD5(T1)_9") (pintype "bidirectional"))
      (node (ref "U5") (pin "6") (pinfunction "PD5/D5/PWM_6") (pintype "bidirectional"))
    )
    (net (code "20") (name "/PD6") (class "Default")
      (node (ref "D5") (pin "2") (pinfunction "2_2") (pintype "bidirectional"))
      (node (ref "D6") (pin "1") (pinfunction "1_1") (pintype "bidirectional"))
      (node (ref "J5") (pin "1") (pinfunction "1_1") (pintype "bidirectional"))
      (node (ref "R55") (pin "2") (pinfunction "2_2") (pintype "passive"))
      (node (ref "SW2") (pin "1B") (pinfunction "B1_1B") (pintype "bidirectional"))
      (node (ref "U4") (pin "10") (pinfunction "PD6(AIN0)_10") (pintype "bidirectional"))
      (node (ref "U5") (pin "7") (pinfunction "PD6/D6/PWM_7") (pintype "bidirectional"))
    )
    (net (code "21") (name "/PD7") (class "Default")
      (node (ref "D6") (pin "2") (pinfunction "2_2") (pintype "bidirectional"))
      (node (ref "D7") (pin "1") (pinfunction "1_1") (pintype "bidirectional"))
      (node (ref "U4") (pin "11") (pinfunction "PD7(AIN1)_11") (pintype "bidirectional"))
      (node (ref "U5") (pin "8") (pinfunction "PD7/D7_8") (pintype "bidirectional"))
    )
    (net (code "22") (name "/PWR_IN") (class "Default")
      (node (ref "U5") (pin "25") (pinfunction "VIN_25") (pintype "bidirectional"))
    )
    (net (code "23") (name "/RESET") (class "Default")
      (node (ref "C10") (pin "2") (pinfunction "2_2") (pintype "passive"))
      (node (ref "R13") (pin "2") (pinfunction "2_2") (pintype "passive"))
      (node (ref "RESET") (pin "2") (pinfunction "2_2") (pintype "bidirectional"))
      (node (ref "RST") (pin "-") (pinfunction "-_-") (pintype "passive"))
      (node (ref "U4") (pin "29") (pinfunction "PC6(/RESET)_29") (pintype "bidirectional"))
      (node (ref "U5") (pin "30") (pinfunction "RESET_30") (pintype "bidirectional"))
      (node (ref "U5") (pin "36") (pinfunction "RST_36") (pintype "bidirectional"))
    )
    (net (code "24") (name "/XTAL1") (class "Default")
      (node (ref "C56") (pin "2") (pinfunction "2_2") (pintype "passive"))
      (node (ref "U4") (pin "7") (pinfunction "PB6(XTAL1/TOSC1)_7") (pintype "bidirectional"))
      (node (ref "X1") (pin "1") (pinfunction "X1_1") (pintype "bidirectional"))
    )
    (net (code "25") (name "/XTAL2") (class "Default")
      (node (ref "C57") (pin "2") (pinfunction "2_2") (pintype "passive"))
      (node (ref "U4") (pin "8") (pinfunction "PB7(XTAL2/TOSC2)_8") (pintype "bidirectional"))
      (node (ref "X1") (pin "3") (pinfunction "X2_3") (pintype "bidirectional"))
    )
    (net (code "26") (name "3V3") (class "Default")
      (node (ref "C15") (pin "1") (pinfunction "1_1") (pintype "passive"))
      (node (ref "C3") (pin "2") (pinfunction "2_2") (pintype "passive"))
      (node (ref "C5") (pin "1") (pinfunction "1_1") (pintype "passive"))
      (node (ref "Q4") (pin "1") (pinfunction "G_1") (pintype "passive"))
      (node (ref "Q5") (pin "1") (pinfunction "G_1") (pintype "passive"))
      (node (ref "R23") (pin "1") (pinfunction "1_1") (pintype "passive"))
      (node (ref "R24") (pin "2") (pinfunction "2_2") (pintype "passive"))
      (node (ref "R25") (pin "2") (pinfunction "2_2") (pintype "passive"))
      (node (ref "U1") (pin "14") (pinfunction "VDD_14") (pintype "bidirectional"))
      (node (ref "U3") (pin "2") (pinfunction "OUT_2") (pintype "bidirectional"))
      (node (ref "U3") (pin "4") (pinfunction "OUT_4") (pintype "bidirectional"))
      (node (ref "U5") (pin "29") (pinfunction "3V3_29") (pintype "bidirectional"))
    )
    (net (code "27") (name "3V3.OLED") (class "Default")
      (node (ref "C43") (pin "1") (pinfunction "1_1") (pintype "passive"))
      (node (ref "C50") (pin "2") (pinfunction "2_2") (pintype "passive"))
      (node (ref "D11") (pin "-") (pinfunction "-_-") (pintype "passive"))
      (node (ref "Q7") (pin "1") (pinfunction "G_1") (pintype "passive"))
      (node (ref "Q8") (pin "1") (pinfunction "G_1") (pintype "passive"))
      (node (ref "R36") (pin "1") (pinfunction "1_1") (pintype "passive"))
      (node (ref "R37") (pin "2") (pinfunction "2_2") (pintype "passive"))
      (node (ref "R40") (pin "2") (pinfunction "2_2") (pintype "passive"))
      (node (ref "R42") (pin "1") (pinfunction "1_1") (pintype "passive"))
      (node (ref "R44") (pin "1") (pinfunction "1_1") (pintype "passive"))
      (node (ref "U7") (pin "2") (pinfunction "VOUT_2") (pintype "bidirectional"))
      (node (ref "U8") (pin "11") (pinfunction "BS1_11") (pintype "input"))
      (node (ref "U8") (pin "9") (pinfunction "VDD_9") (pintype "power_in"))
    )
    (net (code "28") (name "3V3_280") (class "Default")
      (node (ref "C17") (pin "1") (pinfunction "1_1") (pintype "passive"))
      (node (ref "C55") (pin "1") (pinfunction "1_1") (pintype "passive"))
      (node (ref "C60") (pin "1") (pinfunction "1_1") (pintype "passive"))
      (node (ref "C61") (pin "1") (pinfunction "1_1") (pintype "passive"))
      (node (ref "INTERFACE") (pin "2") (pinfunction "2_2") (pintype "bidirectional"))
      (node (ref "Q10") (pin "1") (pinfunction "G_1") (pintype "passive"))
      (node (ref "Q11") (pin "1") (pinfunction "G_1") (pintype "passive"))
      (node (ref "R54") (pin "2") (pinfunction "2_2") (pintype "passive"))
      (node (ref "R59") (pin "2") (pinfunction "2_2") (pintype "passive"))
      (node (ref "R60") (pin "1") (pinfunction "1_1") (pintype "passive"))
      (node (ref "R61") (pin "1") (pinfunction "1_1") (pintype "passive"))
      (node (ref "U12") (pin "5") (pinfunction "SDO_5") (pintype "bidirectional"))
      (node (ref "U12") (pin "6") (pinfunction "VDDIO_6") (pintype "power_in"))
      (node (ref "U12") (pin "8") (pinfunction "VDD_8") (pintype "power_in"))
      (node (ref "U13") (pin "2") (pinfunction "VOUT_2") (pintype "bidirectional"))
    )
    (net (code "29") (name "ADC1") (class "Default")
      (node (ref "TP11") (pin "T") (pinfunction "T_T") (pintype "bidirectional"))
      (node (ref "U1") (pin "16") (pinfunction "ADC1_16") (pintype "bidirectional"))
    )
    (net (code "30") (name "ADC2") (class "Default")
      (node (ref "TP12") (pin "T") (pinfunction "T_T") (pintype "bidirectional"))
      (node (ref "U1") (pin "15") (pinfunction "ADC2_15") (pintype "bidirectional"))
    )
    (net (code "31") (name "ADC3") (class "Default")
      (node (ref "TP13") (pin "T") (pinfunction "T_T") (pintype "bidirectional"))
      (node (ref "U1") (pin "13") (pinfunction "ADC3_13") (pintype "bidirectional"))
    )
    (net (code "32") (name "DTR") (class "Default")
      (node (ref "C10") (pin "1") (pinfunction "1_1") (pintype "passive"))
      (node (ref "U6") (pin "23") (pinfunction "~{DTR}_23") (pintype "bidirectional"))
    )
    (net (code "33") (name "GND") (class "Default")
      (node (ref "A0") (pin "4") (pinfunction "4_4") (pintype "bidirectional"))
      (node (ref "A2") (pin "4") (pinfunction "4_4") (pintype "bidirectional"))
      (node (ref "A6") (pin "4") (pinfunction "4_4") (pintype "bidirectional"))
      (node (ref "C1") (pin "1") (pinfunction "1_1") (pintype "passive"))
      (node (ref "C11") (pin "2") (pinfunction "2_2") (pintype "passive"))
      (node (ref "C12") (pin "2") (pinfunction "2_2") (pintype "passive"))
      (node (ref "C13") (pin "2") (pinfunction "2_2") (pintype "passive"))
      (node (ref "C14") (pin "2") (pinfunction "2_2") (pintype "passive"))
      (node (ref "C15") (pin "2") (pinfunction "2_2") (pintype "passive"))
      (node (ref "C16") (pin "2") (pinfunction "2_2") (pintype "passive"))
      (node (ref "C17") (pin "2") (pinfunction "2_2") (pintype "passive"))
      (node (ref "C18") (pin "1") (pinfunction "1_1") (pintype "passive"))
      (node (ref "C19") (pin "1") (pinfunction "1_1") (pintype "passive"))
      (node (ref "C2") (pin "1") (pinfunction "1_1") (pintype "passive"))
      (node (ref "C20") (pin "1") (pinfunction "1_1") (pintype "passive"))
      (node (ref "C21") (pin "1") (pinfunction "1_1") (pintype "passive"))
      (node (ref "C22") (pin "1") (pinfunction "1_1") (pintype "passive"))
      (node (ref "C23") (pin "1") (pinfunction "1_1") (pintype "passive"))
      (node (ref "C24") (pin "1") (pinfunction "1_1") (pintype "passive"))
      (node (ref "C25") (pin "1") (pinfunction "1_1") (pintype "passive"))
      (node (ref "C26") (pin "2") (pinfunction "2_2") (pintype "passive"))
      (node (ref "C27") (pin "2") (pinfunction "2_2") (pintype "passive"))
      (node (ref "C28") (pin "2") (pinfunction "2_2") (pintype "passive"))
      (node (ref "C29") (pin "2") (pinfunction "2_2") (pintype "passive"))
      (node (ref "C3") (pin "1") (pinfunction "1_1") (pintype "passive"))
      (node (ref "C30") (pin "2") (pinfunction "2_2") (pintype "passive"))
      (node (ref "C31") (pin "2") (pinfunction "2_2") (pintype "passive"))
      (node (ref "C32") (pin "2") (pinfunction "2_2") (pintype "passive"))
      (node (ref "C33") (pin "2") (pinfunction "2_2") (pintype "passive"))
      (node (ref "C34") (pin "1") (pinfunction "1_1") (pintype "passive"))
      (node (ref "C35") (pin "1") (pinfunction "1_1") (pintype "passive"))
      (node (ref "C36") (pin "1") (pinfunction "1_1") (pintype "passive"))
      (node (ref "C37") (pin "1") (pinfunction "1_1") (pintype "passive"))
      (node (ref "C38") (pin "1") (pinfunction "1_1") (pintype "passive"))
      (node (ref "C39") (pin "1") (pinfunction "1_1") (pintype "passive"))
      (node (ref "C4") (pin "1") (pinfunction "1_1") (pintype "passive"))
      (node (ref "C40") (pin "2") (pinfunction "2_2") (pintype "passive"))
      (node (ref "C41") (pin "2") (pinfunction "2_2") (pintype "passive"))
      (node (ref "C42") (pin "2") (pinfunction "2_2") (pintype "passive"))
      (node (ref "C43") (pin "2") (pinfunction "2_2") (pintype "passive"))
      (node (ref "C46") (pin "2") (pinfunction "2_2") (pintype "passive"))
      (node (ref "C47") (pin "1") (pinfunction "1_1") (pintype "passive"))
      (node (ref "C48") (pin "1") (pinfunction "1_1") (pintype "passive"))
      (node (ref "C49") (pin "1") (pinfunction "1_1") (pintype "passive"))
      (node (ref "C5") (pin "2") (pinfunction "2_2") (pintype "passive"))
      (node (ref "C50") (pin "1") (pinfunction "1_1") (pintype "passive"))
      (node (ref "C51") (pin "2") (pinfunction "2_2") (pintype "passive"))
      (node (ref "C54") (pin "2") (pinfunction "2_2") (pintype "bidirectional"))
      (node (ref "C55") (pin "2") (pinfunction "2_2") (pintype "passive"))
      (node (ref "C56") (pin "1") (pinfunction "1_1") (pintype "passive"))
      (node (ref "C57") (pin "1") (pinfunction "1_1") (pintype "passive"))
      (node (ref "C58") (pin "2") (pinfunction "2_2") (pintype "passive"))
      (node (ref "C59") (pin "2") (pinfunction "2_2") (pintype "passive"))
      (node (ref "C6") (pin "1") (pinfunction "1_1") (pintype "passive"))
      (node (ref "C60") (pin "2") (pinfunction "2_2") (pintype "passive"))
      (node (ref "C61") (pin "2") (pinfunction "2_2") (pintype "passive"))
      (node (ref "C7") (pin "1") (pinfunction "1_1") (pintype "passive"))
      (node (ref "C8") (pin "1") (pinfunction "1_1") (pintype "passive"))
      (node (ref "C9") (pin "1") (pinfunction "1_1") (pintype "passive"))
      (node (ref "D1") (pin "2") (pinfunction "1_2") (pintype "bidirectional"))
      (node (ref "D2") (pin "4") (pinfunction "4_4") (pintype "bidirectional"))
      (node (ref "D3") (pin "4") (pinfunction "4_4") (pintype "bidirectional"))
      (node (ref "D4") (pin "4") (pinfunction "4_4") (pintype "bidirectional"))
      (node (ref "D5") (pin "4") (pinfunction "4_4") (pintype "bidirectional"))
      (node (ref "D6") (pin "4") (pinfunction "4_4") (pintype "bidirectional"))
      (node (ref "D7") (pin "4") (pinfunction "4_4") (pintype "bidirectional"))
      (node (ref "D8") (pin "2") (pinfunction "1_2") (pintype "bidirectional"))
      (node (ref "D9") (pin "2") (pinfunction "1_2") (pintype "bidirectional"))
      (node (ref "GND") (pin "T") (pinfunction "T_T") (pintype "bidirectional"))
      (node (ref "GND1") (pin "T") (pinfunction "T_T") (pintype "bidirectional"))
      (node (ref "GND2") (pin "T") (pinfunction "T_T") (pintype "bidirectional"))
      (node (ref "GND4") (pin "T") (pinfunction "T_T") (pintype "bidirectional"))
      (node (ref "I2C.") (pin "4") (pinfunction "4_4") (pintype "bidirectional"))
      (node (ref "I2C..") (pin "4") (pinfunction "4_4") (pintype "bidirectional"))
      (node (ref "J1") (pin "4") (pinfunction "4_4") (pintype "bidirectional"))
      (node (ref "J10") (pin "4") (pinfunction "4_4") (pintype "bidirectional"))
      (node (ref "J11") (pin "4") (pinfunction "4_4") (pintype "bidirectional"))
      (node (ref "J12") (pin "4") (pinfunction "4_4") (pintype "bidirectional"))
      (node (ref "J3") (pin "5") (pinfunction "GND_5") (pintype "bidirectional"))
      (node (ref "J3") (pin "P1") (pinfunction "GND_P1") (pintype "bidirectional"))
      (node (ref "J3") (pin "P3") (pinfunction "GND_P3") (pintype "bidirectional"))
      (node (ref "J3") (pin "P4") (pinfunction "GND_P4") (pintype "bidirectional"))
      (node (ref "J3") (pin "P5") (pinfunction "GND_P5") (pintype "bidirectional"))
      (node (ref "J3") (pin "P6") (pinfunction "GND_P6") (pintype "bidirectional"))
      (node (ref "J4") (pin "4") (pinfunction "4_4") (pintype "bidirectional"))
      (node (ref "J5") (pin "4") (pinfunction "4_4") (pintype "bidirectional"))
      (node (ref "J6") (pin "4") (pinfunction "4_4") (pintype "bidirectional"))
      (node (ref "J7") (pin "4") (pinfunction "4_4") (pintype "bidirectional"))
      (node (ref "J8") (pin "4") (pinfunction "4_4") (pintype "bidirectional"))
      (node (ref "J9") (pin "4") (pinfunction "4_4") (pintype "bidirectional"))
      (node (ref "L") (pin "-") (pinfunction "-_-") (pintype "passive"))
      (node (ref "MIC1") (pin "-") (pinfunction "-_-") (pintype "bidirectional"))
      (node (ref "PWR") (pin "-") (pinfunction "-_-") (pintype "passive"))
      (node (ref "Q6") (pin "2") (pinfunction "E_2") (pintype "passive"))
      (node (ref "Q9") (pin "2") (pinfunction "E_2") (pintype "passive"))
      (node (ref "R2") (pin "1") (pinfunction "1_1") (pintype "passive"))
      (node (ref "R35") (pin "2") (pinfunction "2_2") (pintype "passive"))
      (node (ref "R41") (pin "2") (pinfunction "2_2") (pintype "passive"))
      (node (ref "R43") (pin "1") (pinfunction "1_1") (pintype "passive"))
      (node (ref "R45") (pin "1") (pinfunction "1_1") (pintype "passive"))
      (node (ref "R46") (pin "2") (pinfunction "2_2") (pintype "passive"))
      (node (ref "R49") (pin "2") (pinfunction "2_2") (pintype "passive"))
      (node (ref "R51") (pin "2") (pinfunction "2_2") (pintype "passive"))
      (node (ref "R55") (pin "1") (pinfunction "1_1") (pintype "passive"))
      (node (ref "R57") (pin "1") (pinfunction "1_1") (pintype "passive"))
      (node (ref "RESET") (pin "1") (pinfunction "1_1") (pintype "bidirectional"))
      (node (ref "RESET") (pin "S1") (pinfunction "S1_S1") (pintype "bidirectional"))
      (node (ref "RESET") (pin "S2") (pinfunction "S2_S2") (pintype "bidirectional"))
      (node (ref "ROTATION") (pin "3") (pinfunction "2_3") (pintype "passive"))
      (node (ref "TP1") (pin "T") (pinfunction "T_T") (pintype "bidirectional"))
      (node (ref "TP15") (pin "T") (pinfunction "T_T") (pintype "bidirectional"))
      (node (ref "TP18") (pin "T") (pinfunction "T_T") (pintype "bidirectional"))
      (node (ref "TP7") (pin "T") (pinfunction "T_T") (pintype "bidirectional"))
      (node (ref "U1") (pin "10") (pinfunction "RES_10") (pintype "bidirectional"))
      (node (ref "U1") (pin "12") (pinfunction "GND_12") (pintype "bidirectional"))
      (node (ref "U1") (pin "5") (pinfunction "GND_5") (pintype "bidirectional"))
      (node (ref "U10") (pin "4") (pinfunction "GND_4") (pintype "power_in"))
      (node (ref "U11") (pin "4") (pinfunction "GND_4") (pintype "bidirectional"))
      (node (ref "U12") (pin "1") (pinfunction "GND_1") (pintype "power_in"))
      (node (ref "U12") (pin "7") (pinfunction "GND_7") (pintype "power_in"))
      (node (ref "U13") (pin "1") (pinfunction "VSS_1") (pintype "bidirectional"))
      (node (ref "U2") (pin "1") (pinfunction "VSS_1") (pintype "power_in"))
      (node (ref "U3") (pin "1") (pinfunction "GND_1") (pintype "bidirectional"))
      (node (ref "U4") (pin "21") (pinfunction "GND_21") (pintype "bidirectional"))
      (node (ref "U4") (pin "3") (pinfunction "GND_3") (pintype "bidirectional"))
      (node (ref "U4") (pin "5") (pinfunction "GND_5") (pintype "bidirectional"))
      (node (ref "U4") (pin "HEAT") (pinfunction "GND_HEAT") (pintype "bidirectional"))
      (node (ref "U5") (pin "15") (pinfunction "GND_15") (pintype "bidirectional"))
      (node (ref "U5") (pin "26") (pinfunction "GND_26") (pintype "bidirectional"))
      (node (ref "U5") (pin "27") (pinfunction "GND_27") (pintype "bidirectional"))
      (node (ref "U5") (pin "35") (pinfunction "GND_35") (pintype "bidirectional"))
      (node (ref "U6") (pin "2") (pinfunction "GND_2") (pintype "bidirectional"))
      (node (ref "U6") (pin "PAD") (pinfunction "GND_PAD") (pintype "bidirectional"))
      (node (ref "U7") (pin "1") (pinfunction "VSS_1") (pintype "bidirectional"))
      (node (ref "U8") (pin "1") (pinfunction "NC/GND_1") (pintype "input"))
      (node (ref "U8") (pin "10") (pinfunction "BS0_10") (pintype "input"))
      (node (ref "U8") (pin "13") (pinfunction "/CS_13") (pintype "input"))
      (node (ref "U8") (pin "29") (pinfunction "VLSS_29") (pintype "power_in"))
      (node (ref "U8") (pin "30") (pinfunction "NC/GND1_30") (pintype "input"))
      (node (ref "U8") (pin "8") (pinfunction "VSS_8") (pintype "power_in"))
      (node (ref "U9") (pin "4") (pinfunction "GND_4") (pintype "power_in"))
      (node (ref "UART") (pin "4") (pinfunction "4_4") (pintype "bidirectional"))
      (node (ref "VCC3") (pin "T") (pinfunction "T_T") (pintype "bidirectional"))
      (node (ref "X1") (pin "2") (pinfunction "GND_2") (pintype "bidirectional"))
      (node (ref "X1") (pin "4") (pinfunction "GND_4") (pintype "bidirectional"))
    )
    (net (code "34") (name "HSDO") (class "Default")
      (node (ref "Q3") (pin "3") (pinfunction "D_3") (pintype "passive"))
      (node (ref "R8") (pin "1") (pinfunction "1_1") (pintype "passive"))
      (node (ref "TP8") (pin "T") (pinfunction "T_T") (pintype "bidirectional"))
    )
    (net (code "35") (name "IIC_ADDR") (class "Default")
      (node (ref "JP1") (pin "MM") (pinfunction "C_MM") (pintype "bidirectional"))
      (node (ref "U8") (pin "15") (pinfunction "D/C_15") (pintype "input"))
    )
    (net (code "36") (name "INT1") (class "Default")
      (node (ref "INT") (pin "1") (pinfunction "1_1") (pintype "bidirectional"))
      (node (ref "U1") (pin "11") (pinfunction "INT1_11") (pintype "bidirectional"))
    )
    (net (code "37") (name "L_3V3") (class "Default")
      (node (ref "C2") (pin "2") (pinfunction "2_2") (pintype "passive"))
      (node (ref "C7") (pin "2") (pinfunction "2_2") (pintype "passive"))
      (node (ref "Q1") (pin "1") (pinfunction "G_1") (pintype "passive"))
      (node (ref "Q2") (pin "1") (pinfunction "G_1") (pintype "passive"))
      (node (ref "Q3") (pin "1") (pinfunction "G_1") (pintype "passive"))
      (node (ref "R1") (pin "1") (pinfunction "1_1") (pintype "passive"))
      (node (ref "R10") (pin "2") (pinfunction "2_2") (pintype "passive"))
      (node (ref "R11") (pin "2") (pinfunction "2_2") (pintype "passive"))
      (node (ref "R7") (pin "2") (pinfunction "2_2") (pintype "passive"))
      (node (ref "U1") (pin "1") (pinfunction "VDD_IO_1") (pintype "bidirectional"))
      (node (ref "U2") (pin "2") (pinfunction "VOUT_2") (pintype "output"))
    )
    (net (code "38") (name "L_CS") (class "Default")
      (node (ref "R1") (pin "2") (pinfunction "2_2") (pintype "passive"))
      (node (ref "TP10") (pin "T") (pinfunction "T_T") (pintype "bidirectional"))
      (node (ref "U1") (pin "8") (pinfunction "CS_8") (pintype "bidirectional"))
    )
    (net (code "39") (name "L_SCK") (class "Default")
      (node (ref "R3") (pin "2") (pinfunction "2_2") (pintype "passive"))
      (node (ref "TP9") (pin "T") (pinfunction "T_T") (pintype "bidirectional"))
    )
    (net (code "40") (name "L_SCL") (class "Default")
      (node (ref "Q2") (pin "2") (pinfunction "S_2") (pintype "passive"))
      (node (ref "R10") (pin "1") (pinfunction "1_1") (pintype "passive"))
      (node (ref "U1") (pin "4") (pinfunction "SCL/SPC_4") (pintype "bidirectional"))
    )
    (net (code "41") (name "L_SDA") (class "Default")
      (node (ref "Q1") (pin "2") (pinfunction "S_2") (pintype "passive"))
      (node (ref "R11") (pin "1") (pinfunction "1_1") (pintype "passive"))
      (node (ref "U1") (pin "6") (pinfunction "SDA/SDI/SDO_6") (pintype "bidirectional"))
    )
    (net (code "42") (name "L_SDI") (class "Default")
      (node (ref "R5") (pin "2") (pinfunction "2_2") (pintype "passive"))
      (node (ref "TP6") (pin "T") (pinfunction "T_T") (pintype "bidirectional"))
    )
    (net (code "43") (name "Net-(BUZ1-Pad-)") (class "Default")
      (node (ref "BUZ1") (pin "-") (pinfunction "-_-") (pintype "bidirectional"))
      (node (ref "R58") (pin "2") (pinfunction "2_2") (pintype "passive"))
      (node (ref "R64") (pin "1") (pinfunction "1_1") (pintype "passive"))
    )
    (net (code "44") (name "Net-(C52-Pad1)") (class "Default")
      (node (ref "C52") (pin "1") (pinfunction "1_1") (pintype "passive"))
      (node (ref "MIC1") (pin "+") (pinfunction "+_+") (pintype "bidirectional"))
      (node (ref "R50") (pin "1") (pinfunction "1_1") (pintype "passive"))
    )
    (net (code "45") (name "Net-(C52-Pad2)") (class "Default")
      (node (ref "C52") (pin "2") (pinfunction "2_2") (pintype "passive"))
      (node (ref "R51") (pin "1") (pinfunction "1_1") (pintype "passive"))
      (node (ref "R52") (pin "1") (pinfunction "1_1") (pintype "passive"))
    )
    (net (code "46") (name "Net-(D8-2)") (class "Default")
      (node (ref "D8") (pin "1") (pinfunction "2_1") (pintype "bidirectional"))
      (node (ref "J3") (pin "2") (pinfunction "DM_2") (pintype "bidirectional"))
      (node (ref "R18") (pin "1") (pinfunction "1_1") (pintype "passive"))
      (node (ref "TP16") (pin "T") (pinfunction "T_T") (pintype "bidirectional"))
    )
    (net (code "47") (name "Net-(D9-2)") (class "Default")
      (node (ref "D9") (pin "1") (pinfunction "2_1") (pintype "bidirectional"))
      (node (ref "J3") (pin "3") (pinfunction "DP_3") (pintype "bidirectional"))
      (node (ref "R17") (pin "1") (pinfunction "1_1") (pintype "passive"))
      (node (ref "TP17") (pin "T") (pinfunction "T_T") (pintype "bidirectional"))
    )
    (net (code "48") (name "Net-(D10-Pad+)") (class "Default")
      (node (ref "D10") (pin "+") (pinfunction "+_+") (pintype "passive"))
      (node (ref "R32") (pin "2") (pinfunction "2_2") (pintype "passive"))
      (node (ref "R34") (pin "1") (pinfunction "1_1") (pintype "passive"))
    )
    (net (code "49") (name "Net-(J3-VCC)") (class "Default")
      (node (ref "F1") (pin "1") (pinfunction "1_1") (pintype "bidirectional"))
      (node (ref "J3") (pin "1") (pinfunction "VCC_1") (pintype "bidirectional"))
      (node (ref "TP14") (pin "T") (pinfunction "T_T") (pintype "bidirectional"))
    )
    (net (code "50") (name "Net-(JP1-L)") (class "Default")
      (node (ref "JP1") (pin "11") (pinfunction "L_11") (pintype "bidirectional"))
      (node (ref "R43") (pin "2") (pinfunction "2_2") (pintype "passive"))
    )
    (net (code "51") (name "Net-(JP1-R)") (class "Default")
      (node (ref "JP1") (pin "00") (pinfunction "R_00") (pintype "bidirectional"))
      (node (ref "R44") (pin "2") (pinfunction "2_2") (pintype "passive"))
    )
    (net (code "52") (name "Net-(L-Pad+)") (class "Default")
      (node (ref "L") (pin "+") (pinfunction "+_+") (pintype "passive"))
      (node (ref "R14") (pin "2") (pinfunction "2_2") (pintype "passive"))
    )
    (net (code "53") (name "Net-(LIGHT-2)") (class "Default")
      (node (ref "LIGHT") (pin "E") (pinfunction "2_E") (pintype "bidirectional"))
      (node (ref "R45") (pin "2") (pinfunction "2_2") (pintype "passive"))
      (node (ref "U9") (pin "3") (pinfunction "+IN1_3") (pintype "input"))
    )
    (net (code "54") (name "Net-(PWR-Pad+)") (class "Default")
      (node (ref "PWR") (pin "+") (pinfunction "+_+") (pintype "passive"))
      (node (ref "R12") (pin "2") (pinfunction "2_2") (pintype "passive"))
    )
    (net (code "55") (name "Net-(Q6-B)") (class "Default")
      (node (ref "Q6") (pin "1") (pinfunction "B_1") (pintype "passive"))
      (node (ref "R33") (pin "2") (pinfunction "2_2") (pintype "passive"))
      (node (ref "R35") (pin "1") (pinfunction "1_1") (pintype "passive"))
    )
    (net (code "56") (name "Net-(Q6-C)") (class "Default")
      (node (ref "D10") (pin "-") (pinfunction "-_-") (pintype "passive"))
      (node (ref "Q6") (pin "3") (pinfunction "C_3") (pintype "passive"))
      (node (ref "R34") (pin "2") (pinfunction "2_2") (pintype "passive"))
      (node (ref "SIG_O") (pin "T") (pinfunction "T_T") (pintype "bidirectional"))
    )
    (net (code "57") (name "Net-(Q9-B)") (class "Default")
      (node (ref "Q9") (pin "1") (pinfunction "B_1") (pintype "passive"))
      (node (ref "R56") (pin "2") (pinfunction "2_2") (pintype "passive"))
      (node (ref "R57") (pin "2") (pinfunction "2_2") (pintype "passive"))
    )
    (net (code "58") (name "Net-(Q9-C)") (class "Default")
      (node (ref "Q9") (pin "3") (pinfunction "C_3") (pintype "passive"))
      (node (ref "R58") (pin "1") (pinfunction "1_1") (pintype "passive"))
    )
    (net (code "59") (name "Net-(R9-Pad2)") (class "Default")
      (node (ref "R9") (pin "2") (pinfunction "2_2") (pintype "passive"))
      (node (ref "RST") (pin "+") (pinfunction "+_+") (pintype "passive"))
    )
    (net (code "60") (name "Net-(R15-Pad1)") (class "Default")
      (node (ref "R15") (pin "1") (pinfunction "1_1") (pintype "passive"))
      (node (ref "RX") (pin "+") (pinfunction "+_+") (pintype "passive"))
    )
    (net (code "61") (name "Net-(R16-Pad1)") (class "Default")
      (node (ref "R16") (pin "1") (pinfunction "1_1") (pintype "passive"))
      (node (ref "TX") (pin "+") (pinfunction "+_+") (pintype "passive"))
    )
    (net (code "62") (name "Net-(R31-2)") (class "Default")
      (node (ref "R31") (pin "2") (pinfunction "3_2") (pintype "passive"))
      (node (ref "R31") (pin "3") (pinfunction "2_3") (pintype "passive"))
      (node (ref "R32") (pin "1") (pinfunction "1_1") (pintype "passive"))
    )
    (net (code "63") (name "Net-(U6-RXD)") (class "Default")
      (node (ref "R20") (pin "1") (pinfunction "1_1") (pintype "passive"))
      (node (ref "U6") (pin "20") (pinfunction "RXD_20") (pintype "bidirectional"))
    )
    (net (code "64") (name "Net-(U6-RXLED{slash}IO1)") (class "Default")
      (node (ref "RX") (pin "-") (pinfunction "-_-") (pintype "passive"))
      (node (ref "U6") (pin "13") (pinfunction "RXLED/IO1_13") (pintype "bidirectional"))
    )
    (net (code "65") (name "Net-(U6-TXD)") (class "Default")
      (node (ref "R19") (pin "1") (pinfunction "1_1") (pintype "passive"))
      (node (ref "U6") (pin "21") (pinfunction "TXD_21") (pintype "bidirectional"))
    )
    (net (code "66") (name "Net-(U6-TXLED{slash}IO0)") (class "Default")
      (node (ref "TX") (pin "-") (pinfunction "-_-") (pintype "passive"))
      (node (ref "U6") (pin "14") (pinfunction "TXLED/IO0_14") (pintype "bidirectional"))
    )
    (net (code "67") (name "Net-(U6-VREGIN)") (class "Default")
      (node (ref "R21") (pin "2") (pinfunction "2_2") (pintype "passive"))
      (node (ref "R22") (pin "2") (pinfunction "2_2") (pintype "passive"))
      (node (ref "U6") (pin "7") (pinfunction "VREGIN_7") (pintype "bidirectional"))
    )
    (net (code "68") (name "Net-(U6-~{RESET})") (class "Default")
      (node (ref "R26") (pin "2") (pinfunction "2_2") (pintype "passive"))
      (node (ref "U6") (pin "9") (pinfunction "~{RESET}_9") (pintype "bidirectional"))
    )
    (net (code "69") (name "Net-(U8-C1N)") (class "Default")
      (node (ref "C45") (pin "1") (pinfunction "1_1") (pintype "passive"))
      (node (ref "U8") (pin "5") (pinfunction "C1N_5") (pintype "input"))
    )
    (net (code "70") (name "Net-(U8-C1P)") (class "Default")
      (node (ref "C45") (pin "2") (pinfunction "2_2") (pintype "passive"))
      (node (ref "U8") (pin "4") (pinfunction "C1P_4") (pintype "input"))
    )
    (net (code "71") (name "Net-(U8-C2N)") (class "Default")
      (node (ref "C44") (pin "1") (pinfunction "1_1") (pintype "passive"))
      (node (ref "U8") (pin "3") (pinfunction "C2N_3") (pintype "input"))
    )
    (net (code "72") (name "Net-(U8-C2P)") (class "Default")
      (node (ref "C44") (pin "2") (pinfunction "2_2") (pintype "passive"))
      (node (ref "U8") (pin "2") (pinfunction "C2P_2") (pintype "input"))
    )
    (net (code "73") (name "Net-(U8-IREF)") (class "Default")
      (node (ref "R41") (pin "1") (pinfunction "1_1") (pintype "passive"))
      (node (ref "U8") (pin "26") (pinfunction "IREF_26") (pintype "input"))
    )
    (net (code "74") (name "Net-(U8-VBAT)") (class "Default")
      (node (ref "R42") (pin "2") (pinfunction "2_2") (pintype "passive"))
      (node (ref "U8") (pin "6") (pinfunction "VBAT_6") (pintype "input"))
    )
    (net (code "75") (name "Net-(U8-VCC)") (class "Default")
      (node (ref "C48") (pin "2") (pinfunction "2_2") (pintype "passive"))
      (node (ref "U8") (pin "28") (pinfunction "VCC_28") (pintype "power_in"))
    )
    (net (code "76") (name "Net-(U8-VCOMH)") (class "Default")
      (node (ref "C47") (pin "2") (pinfunction "2_2") (pintype "passive"))
      (node (ref "U8") (pin "27") (pinfunction "VCOMH_27") (pintype "output"))
    )
    (net (code "77") (name "Net-(U10A-+IN1)") (class "Default")
      (node (ref "R48") (pin "1") (pinfunction "1_1") (pintype "passive"))
      (node (ref "U10") (pin "3") (pinfunction "+IN1_3") (pintype "input"))
      (node (ref "U10") (pin "7") (pinfunction "OUT2_7") (pintype "output"))
    )
    (net (code "78") (name "Net-(U10A--IN1)") (class "Default")
      (node (ref "R46") (pin "1") (pinfunction "1_1") (pintype "passive"))
      (node (ref "R47") (pin "2") (pinfunction "2_2") (pintype "passive"))
      (node (ref "U10") (pin "2") (pinfunction "-IN1_2") (pintype "input"))
    )
    (net (code "79") (name "Net-(U10A-OUT1)") (class "Default")
      (node (ref "C53") (pin "1") (pinfunction "1_1") (pintype "passive"))
      (node (ref "R47") (pin "1") (pinfunction "1_1") (pintype "passive"))
      (node (ref "U10") (pin "1") (pinfunction "OUT1_1") (pintype "output"))
    )
    (net (code "80") (name "Net-(U10B-+IN2)") (class "Default")
      (node (ref "R52") (pin "2") (pinfunction "2_2") (pintype "passive"))
      (node (ref "U10") (pin "5") (pinfunction "+IN2_5") (pintype "input"))
    )
    (net (code "81") (name "Net-(U10B--IN2)") (class "Default")
      (node (ref "R48") (pin "2") (pinfunction "2_2") (pintype "passive"))
      (node (ref "R49") (pin "1") (pinfunction "1_1") (pintype "passive"))
      (node (ref "U10") (pin "6") (pinfunction "-IN2_6") (pintype "input"))
    )
    (net (code "82") (name "Net-(U12-CSB)") (class "Default")
      (node (ref "INTERFACE") (pin "1") (pinfunction "1_1") (pintype "bidirectional"))
      (node (ref "U12") (pin "2") (pinfunction "CSB_2") (pintype "bidirectional"))
    )
    (net (code "83") (name "PC4{slash}SDA") (class "Default")
      (node (ref "I2C.") (pin "2") (pinfunction "2_2") (pintype "bidirectional"))
      (node (ref "I2C..") (pin "2") (pinfunction "2_2") (pintype "bidirectional"))
      (node (ref "J1") (pin "2") (pinfunction "2_2") (pintype "bidirectional"))
      (node (ref "J10") (pin "2") (pinfunction "2_2") (pintype "bidirectional"))
      (node (ref "J4") (pin "2") (pinfunction "2_2") (pintype "bidirectional"))
      (node (ref "Q1") (pin "3") (pinfunction "D_3") (pintype "passive"))
      (node (ref "Q10") (pin "3") (pinfunction "D_3") (pintype "passive"))
      (node (ref "Q7") (pin "3") (pinfunction "D_3") (pintype "passive"))
      (node (ref "R29") (pin "2") (pinfunction "2_2") (pintype "passive"))
      (node (ref "R38") (pin "1") (pinfunction "1_1") (pintype "passive"))
      (node (ref "R5") (pin "1") (pinfunction "1_1") (pintype "passive"))
      (node (ref "R6") (pin "1") (pinfunction "1_1") (pintype "passive"))
      (node (ref "R63") (pin "2") (pinfunction "2_2") (pintype "passive"))
      (node (ref "TP3") (pin "T") (pinfunction "T_T") (pintype "bidirectional"))
      (node (ref "U4") (pin "27") (pinfunction "PC4(ADC4/SDA)_27") (pintype "bidirectional"))
      (node (ref "U5") (pin "17") (pinfunction "SDA_17") (pintype "bidirectional"))
      (node (ref "U5") (pin "23") (pinfunction "PC4/AD4/D18/SDA_23") (pintype "bidirectional"))
    )
    (net (code "84") (name "PC5{slash}SCL") (class "Default")
      (node (ref "I2C.") (pin "1") (pinfunction "1_1") (pintype "bidirectional"))
      (node (ref "I2C..") (pin "1") (pinfunction "1_1") (pintype "bidirectional"))
      (node (ref "J1") (pin "1") (pinfunction "1_1") (pintype "bidirectional"))
      (node (ref "J10") (pin "1") (pinfunction "1_1") (pintype "bidirectional"))
      (node (ref "J4") (pin "1") (pinfunction "1_1") (pintype "bidirectional"))
      (node (ref "Q11") (pin "3") (pinfunction "D_3") (pintype "passive"))
      (node (ref "Q2") (pin "3") (pinfunction "D_3") (pintype "passive"))
      (node (ref "Q8") (pin "3") (pinfunction "D_3") (pintype "passive"))
      (node (ref "R3") (pin "1") (pinfunction "1_1") (pintype "passive"))
      (node (ref "R30") (pin "2") (pinfunction "2_2") (pintype "passive"))
      (node (ref "R39") (pin "1") (pinfunction "1_1") (pintype "passive"))
      (node (ref "R4") (pin "1") (pinfunction "1_1") (pintype "passive"))
      (node (ref "R62") (pin "2") (pinfunction "2_2") (pintype "passive"))
      (node (ref "TP4") (pin "T") (pinfunction "T_T") (pintype "bidirectional"))
      (node (ref "U4") (pin "28") (pinfunction "PC5(ADC5/SCL)_28") (pintype "bidirectional"))
      (node (ref "U5") (pin "18") (pinfunction "SCL_18") (pintype "bidirectional"))
      (node (ref "U5") (pin "24") (pinfunction "PC5/AD5/D19/SCL_24") (pintype "bidirectional"))
    )
    (net (code "85") (name "PD0{slash}RX") (class "Default")
      (node (ref "Q4") (pin "3") (pinfunction "D_3") (pintype "passive"))
      (node (ref "R27") (pin "1") (pinfunction "1_1") (pintype "passive"))
      (node (ref "U4") (pin "30") (pinfunction "PD0(RXD)_30") (pintype "bidirectional"))
      (node (ref "U5") (pin "1") (pinfunction "PD0/D0/RX_1") (pintype "bidirectional"))
      (node (ref "UART") (pin "1") (pinfunction "1_1") (pintype "bidirectional"))
    )
    (net (code "86") (name "PD1{slash}TX") (class "Default")
      (node (ref "Q5") (pin "3") (pinfunction "D_3") (pintype "passive"))
      (node (ref "R28") (pin "1") (pinfunction "1_1") (pintype "passive"))
      (node (ref "U4") (pin "31") (pinfunction "PD1(TXD)_31") (pintype "bidirectional"))
      (node (ref "U5") (pin "2") (pinfunction "PD1/D1/TX_2") (pintype "bidirectional"))
      (node (ref "UART") (pin "2") (pinfunction "2_2") (pintype "bidirectional"))
    )
    (net (code "87") (name "RES") (class "Default")
      (node (ref "C46") (pin "1") (pinfunction "1_1") (pintype "passive"))
      (node (ref "D11") (pin "+") (pinfunction "+_+") (pintype "passive"))
      (node (ref "R40") (pin "1") (pinfunction "1_1") (pintype "passive"))
      (node (ref "U8") (pin "14") (pinfunction "/RES_14") (pintype "input"))
    )
    (net (code "88") (name "SCL") (class "Default")
      (node (ref "Q8") (pin "2") (pinfunction "S_2") (pintype "passive"))
      (node (ref "R37") (pin "1") (pinfunction "1_1") (pintype "passive"))
      (node (ref "U8") (pin "18") (pinfunction "D0/SCLK_18") (pintype "bidirectional"))
    )
    (net (code "89") (name "SCL_3V3") (class "Default")
      (node (ref "Q11") (pin "2") (pinfunction "S_2") (pintype "passive"))
      (node (ref "R59") (pin "1") (pinfunction "1_1") (pintype "passive"))
      (node (ref "R60") (pin "2") (pinfunction "2_2") (pintype "passive"))
      (node (ref "U12") (pin "4") (pinfunction "SCK_4") (pintype "bidirectional"))
    )
    (net (code "90") (name "SDA") (class "Default")
      (node (ref "Q7") (pin "2") (pinfunction "S_2") (pintype "passive"))
      (node (ref "R36") (pin "2") (pinfunction "2_2") (pintype "passive"))
      (node (ref "U8") (pin "19") (pinfunction "D1/SDIN_19") (pintype "bidirectional"))
      (node (ref "U8") (pin "20") (pinfunction "D2_20") (pintype "input"))
    )
    (net (code "91") (name "SDA_3V3") (class "Default")
      (node (ref "Q10") (pin "2") (pinfunction "S_2") (pintype "passive"))
      (node (ref "R54") (pin "1") (pinfunction "1_1") (pintype "passive"))
      (node (ref "R61") (pin "2") (pinfunction "2_2") (pintype "passive"))
      (node (ref "U12") (pin "3") (pinfunction "SDI_3") (pintype "bidirectional"))
    )
    (net (code "92") (name "UART_RX") (class "Default")
      (node (ref "Q4") (pin "2") (pinfunction "S_2") (pintype "passive"))
      (node (ref "R19") (pin "2") (pinfunction "2_2") (pintype "passive"))
      (node (ref "R24") (pin "1") (pinfunction "1_1") (pintype "passive"))
    )
    (net (code "93") (name "UART_TX") (class "Default")
      (node (ref "Q5") (pin "2") (pinfunction "S_2") (pintype "passive"))
      (node (ref "R20") (pin "2") (pinfunction "2_2") (pintype "passive"))
      (node (ref "R25") (pin "1") (pinfunction "1_1") (pintype "passive"))
    )
    (net (code "94") (name "USB_D") (class "Default")
      (node (ref "R18") (pin "2") (pinfunction "2_2") (pintype "passive"))
      (node (ref "U6") (pin "4") (pinfunction "D-_4") (pintype "bidirectional"))
    )
    (net (code "95") (name "USB_D+") (class "Default")
      (node (ref "R17") (pin "2") (pinfunction "2_2") (pintype "passive"))
      (node (ref "U6") (pin "3") (pinfunction "D+_3") (pintype "bidirectional"))
    )
    (net (code "96") (name "VCC") (class "Default")
      (node (ref "A0") (pin "3") (pinfunction "3_3") (pintype "bidirectional"))
      (node (ref "A2") (pin "3") (pinfunction "3_3") (pintype "bidirectional"))
      (node (ref "A6") (pin "3") (pinfunction "3_3") (pintype "bidirectional"))
      (node (ref "BUZ1") (pin "+") (pinfunction "+_+") (pintype "bidirectional"))
      (node (ref "C1") (pin "2") (pinfunction "2_2") (pintype "passive"))
      (node (ref "C11") (pin "1") (pinfunction "1_1") (pintype "passive"))
      (node (ref "C12") (pin "1") (pinfunction "1_1") (pintype "passive"))
      (node (ref "C16") (pin "1") (pinfunction "1_1") (pintype "passive"))
      (node (ref "C18") (pin "2") (pinfunction "2_2") (pintype "passive"))
      (node (ref "C19") (pin "2") (pinfunction "2_2") (pintype "passive"))
      (node (ref "C20") (pin "2") (pinfunction "2_2") (pintype "passive"))
      (node (ref "C21") (pin "2") (pinfunction "2_2") (pintype "passive"))
      (node (ref "C22") (pin "2") (pinfunction "2_2") (pintype "passive"))
      (node (ref "C23") (pin "2") (pinfunction "2_2") (pintype "passive"))
      (node (ref "C24") (pin "2") (pinfunction "2_2") (pintype "passive"))
      (node (ref "C25") (pin "2") (pinfunction "2_2") (pintype "passive"))
      (node (ref "C26") (pin "1") (pinfunction "1_1") (pintype "passive"))
      (node (ref "C27") (pin "1") (pinfunction "1_1") (pintype "passive"))
      (node (ref "C28") (pin "1") (pinfunction "1_1") (pintype "passive"))
      (node (ref "C29") (pin "1") (pinfunction "1_1") (pintype "passive"))
      (node (ref "C30") (pin "1") (pinfunction "1_1") (pintype "passive"))
      (node (ref "C31") (pin "1") (pinfunction "1_1") (pintype "passive"))
      (node (ref "C32") (pin "1") (pinfunction "1_1") (pintype "passive"))
      (node (ref "C33") (pin "1") (pinfunction "1_1") (pintype "passive"))
      (node (ref "C34") (pin "2") (pinfunction "2_2") (pintype "passive"))
      (node (ref "C35") (pin "2") (pinfunction "2_2") (pintype "passive"))
      (node (ref "C36") (pin "2") (pinfunction "2_2") (pintype "passive"))
      (node (ref "C37") (pin "2") (pinfunction "2_2") (pintype "passive"))
      (node (ref "C38") (pin "2") (pinfunction "2_2") (pintype "passive"))
      (node (ref "C39") (pin "2") (pinfunction "2_2") (pintype "passive"))
      (node (ref "C4") (pin "2") (pinfunction "2_2") (pintype "passive"))
      (node (ref "C40") (pin "1") (pinfunction "1_1") (pintype "passive"))
      (node (ref "C41") (pin "1") (pinfunction "1_1") (pintype "passive"))
      (node (ref "C42") (pin "1") (pinfunction "1_1") (pintype "passive"))
      (node (ref "C49") (pin "2") (pinfunction "2_2") (pintype "passive"))
      (node (ref "C51") (pin "1") (pinfunction "1_1") (pintype "passive"))
      (node (ref "C54") (pin "1") (pinfunction "1_1") (pintype "bidirectional"))
      (node (ref "C58") (pin "1") (pinfunction "1_1") (pintype "passive"))
      (node (ref "C59") (pin "1") (pinfunction "1_1") (pintype "passive"))
      (node (ref "C6") (pin "2") (pinfunction "2_2") (pintype "passive"))
      (node (ref "C9") (pin "2") (pinfunction "2_2") (pintype "passive"))
      (node (ref "D1") (pin "1") (pinfunction "2_1") (pintype "bidirectional"))
      (node (ref "D2") (pin "3") (pinfunction "3_3") (pintype "bidirectional"))
      (node (ref "D3") (pin "3") (pinfunction "3_3") (pintype "bidirectional"))
      (node (ref "D4") (pin "3") (pinfunction "3_3") (pintype "bidirectional"))
      (node (ref "D5") (pin "3") (pinfunction "3_3") (pintype "bidirectional"))
      (node (ref "D6") (pin "3") (pinfunction "3_3") (pintype "bidirectional"))
      (node (ref "D7") (pin "3") (pinfunction "3_3") (pintype "bidirectional"))
      (node (ref "F1") (pin "2") (pinfunction "2_2") (pintype "bidirectional"))
      (node (ref "GND3") (pin "T") (pinfunction "T_T") (pintype "bidirectional"))
      (node (ref "I2C.") (pin "3") (pinfunction "3_3") (pintype "bidirectional"))
      (node (ref "I2C..") (pin "3") (pinfunction "3_3") (pintype "bidirectional"))
      (node (ref "J1") (pin "3") (pinfunction "3_3") (pintype "bidirectional"))
      (node (ref "J10") (pin "3") (pinfunction "3_3") (pintype "bidirectional"))
      (node (ref "J11") (pin "3") (pinfunction "3_3") (pintype "bidirectional"))
      (node (ref "J12") (pin "3") (pinfunction "3_3") (pintype "bidirectional"))
      (node (ref "J4") (pin "3") (pinfunction "3_3") (pintype "bidirectional"))
      (node (ref "J5") (pin "3") (pinfunction "3_3") (pintype "bidirectional"))
      (node (ref "J6") (pin "3") (pinfunction "3_3") (pintype "bidirectional"))
      (node (ref "J7") (pin "3") (pinfunction "3_3") (pintype "bidirectional"))
      (node (ref "J8") (pin "3") (pinfunction "3_3") (pintype "bidirectional"))
      (node (ref "J9") (pin "3") (pinfunction "3_3") (pintype "bidirectional"))
      (node (ref "LIGHT") (pin "C") (pinfunction "1_C") (pintype "bidirectional"))
      (node (ref "R12") (pin "1") (pinfunction "1_1") (pintype "passive"))
      (node (ref "R13") (pin "1") (pinfunction "1_1") (pintype "passive"))
      (node (ref "R21") (pin "1") (pinfunction "1_1") (pintype "passive"))
      (node (ref "R26") (pin "1") (pinfunction "1_1") (pintype "passive"))
      (node (ref "R27") (pin "2") (pinfunction "2_2") (pintype "passive"))
      (node (ref "R28") (pin "2") (pinfunction "2_2") (pintype "passive"))
      (node (ref "R29") (pin "1") (pinfunction "1_1") (pintype "passive"))
      (node (ref "R30") (pin "1") (pinfunction "1_1") (pintype "passive"))
      (node (ref "R31") (pin "1") (pinfunction "1_1") (pintype "passive"))
      (node (ref "R38") (pin "2") (pinfunction "2_2") (pintype "passive"))
      (node (ref "R39") (pin "2") (pinfunction "2_2") (pintype "passive"))
      (node (ref "R4") (pin "2") (pinfunction "2_2") (pintype "passive"))
      (node (ref "R50") (pin "2") (pinfunction "2_2") (pintype "passive"))
      (node (ref "R53") (pin "2") (pinfunction "2_2") (pintype "bidirectional"))
      (node (ref "R6") (pin "2") (pinfunction "2_2") (pintype "passive"))
      (node (ref "R62") (pin "1") (pinfunction "1_1") (pintype "passive"))
      (node (ref "R63") (pin "1") (pinfunction "1_1") (pintype "passive"))
      (node (ref "R64") (pin "2") (pinfunction "2_2") (pintype "passive"))
      (node (ref "R8") (pin "2") (pinfunction "2_2") (pintype "passive"))
      (node (ref "R9") (pin "1") (pinfunction "1_1") (pintype "passive"))
      (node (ref "ROTATION") (pin "1") (pinfunction "1_1") (pintype "passive"))
      (node (ref "SW2") (pin "0A") (pinfunction "A0_0A") (pintype "bidirectional"))
      (node (ref "TP19") (pin "T") (pinfunction "T_T") (pintype "bidirectional"))
      (node (ref "TP2") (pin "T") (pinfunction "T_T") (pintype "bidirectional"))
      (node (ref "TP5") (pin "T") (pinfunction "T_T") (pintype "bidirectional"))
      (node (ref "U10") (pin "8") (pinfunction "+V_8") (pintype "power_in"))
      (node (ref "U11") (pin "1") (pinfunction "VCC_1") (pintype "bidirectional"))
      (node (ref "U13") (pin "3") (pinfunction "VIN_3") (pintype "bidirectional"))
      (node (ref "U2") (pin "3") (pinfunction "VIN_3") (pintype "input"))
      (node (ref "U3") (pin "3") (pinfunction "IN_3") (pintype "bidirectional"))
      (node (ref "U4") (pin "18") (pinfunction "AVCC_18") (pintype "bidirectional"))
      (node (ref "U4") (pin "4") (pinfunction "VCC_4") (pintype "bidirectional"))
      (node (ref "U4") (pin "6") (pinfunction "VCC_6") (pintype "bidirectional"))
      (node (ref "U5") (pin "28") (pinfunction "5V_28") (pintype "bidirectional"))
      (node (ref "U5") (pin "31") (pinfunction "ADC7_31") (pintype "bidirectional"))
      (node (ref "U5") (pin "33") (pinfunction "VCC_33") (pintype "bidirectional"))
      (node (ref "U6") (pin "8") (pinfunction "VBUS_8") (pintype "bidirectional"))
      (node (ref "U7") (pin "3") (pinfunction "VIN_3") (pintype "bidirectional"))
      (node (ref "U9") (pin "8") (pinfunction "+V_8") (pintype "power_in"))
      (node (ref "UART") (pin "3") (pinfunction "3_3") (pintype "bidirectional"))
      (node (ref "VCC") (pin "T") (pinfunction "T_T") (pintype "bidirectional"))
      (node (ref "VCC1") (pin "T") (pinfunction "T_T") (pintype "bidirectional"))
      (node (ref "VCC2") (pin "T") (pinfunction "T_T") (pintype "bidirectional"))
      (node (ref "VCC4") (pin "T") (pinfunction "T_T") (pintype "bidirectional"))
    )
    (net (code "97") (name "VIO") (class "Default")
      (node (ref "C13") (pin "1") (pinfunction "1_1") (pintype "passive"))
      (node (ref "C14") (pin "1") (pinfunction "1_1") (pintype "passive"))
      (node (ref "R15") (pin "2") (pinfunction "2_2") (pintype "passive"))
      (node (ref "R16") (pin "2") (pinfunction "2_2") (pintype "passive"))
      (node (ref "R22") (pin "1") (pinfunction "1_1") (pintype "passive"))
      (node (ref "R23") (pin "2") (pinfunction "2_2") (pintype "passive"))
      (node (ref "U6") (pin "5") (pinfunction "VIO_5") (pintype "bidirectional"))
      (node (ref "U6") (pin "6") (pinfunction "VDD_6") (pintype "bidirectional"))
    )
    (net (code "98") (name "unconnected-(J3-ID-Pad4)") (class "Default")
      (node (ref "J3") (pin "4") (pinfunction "ID_4") (pintype "bidirectional"))
    )
    (net (code "99") (name "unconnected-(J5-Pad2)") (class "Default")
      (node (ref "J5") (pin "2") (pinfunction "2_2") (pintype "bidirectional"))
    )
    (net (code "100") (name "unconnected-(J7-Pad2)") (class "Default")
      (node (ref "J7") (pin "2") (pinfunction "2_2") (pintype "bidirectional"))
    )
    (net (code "101") (name "unconnected-(J8-Pad2)") (class "Default")
      (node (ref "J8") (pin "2") (pinfunction "2_2") (pintype "bidirectional"))
    )
    (net (code "102") (name "unconnected-(J9-Pad2)") (class "Default")
      (node (ref "J9") (pin "2") (pinfunction "2_2") (pintype "bidirectional"))
    )
    (net (code "103") (name "unconnected-(J11-Pad2)") (class "Default")
      (node (ref "J11") (pin "2") (pinfunction "2_2") (pintype "bidirectional"))
    )
    (net (code "104") (name "unconnected-(J12-Pad2)") (class "Default")
      (node (ref "J12") (pin "2") (pinfunction "2_2") (pintype "bidirectional"))
    )
    (net (code "105") (name "unconnected-(NC1-PadT)") (class "Default")
      (node (ref "NC1") (pin "T") (pinfunction "T_T") (pintype "bidirectional"))
    )
    (net (code "106") (name "unconnected-(NC2-PadT)") (class "Default")
      (node (ref "NC2") (pin "T") (pinfunction "T_T") (pintype "bidirectional"))
    )
    (net (code "107") (name "unconnected-(NC3-PadT)") (class "Default")
      (node (ref "NC3") (pin "T") (pinfunction "T_T") (pintype "bidirectional"))
    )
    (net (code "108") (name "unconnected-(NC4-PadT)") (class "Default")
      (node (ref "NC4") (pin "T") (pinfunction "T_T") (pintype "bidirectional"))
    )
    (net (code "109") (name "unconnected-(NC5-PadT)") (class "Default")
      (node (ref "NC5") (pin "T") (pinfunction "T_T") (pintype "bidirectional"))
    )
    (net (code "110") (name "unconnected-(NC6-PadT)") (class "Default")
      (node (ref "NC6") (pin "T") (pinfunction "T_T") (pintype "bidirectional"))
    )
    (net (code "111") (name "unconnected-(SIG4-PadT)") (class "Default")
      (node (ref "SIG4") (pin "T") (pinfunction "T_T") (pintype "bidirectional"))
    )
    (net (code "112") (name "unconnected-(SW2-A1-Pad1A)") (class "Default")
      (node (ref "SW2") (pin "1A") (pinfunction "A1_1A") (pintype "bidirectional"))
    )
    (net (code "113") (name "unconnected-(SW2-B0-Pad0B)") (class "Default")
      (node (ref "SW2") (pin "0B") (pinfunction "B0_0B") (pintype "bidirectional"))
    )
    (net (code "114") (name "unconnected-(TP20-PadT)") (class "Default")
      (node (ref "TP20") (pin "T") (pinfunction "T_T") (pintype "bidirectional"))
    )
    (net (code "115") (name "unconnected-(U1-INT2-Pad9)") (class "Default")
      (node (ref "U1") (pin "9") (pinfunction "INT2_9") (pintype "bidirectional"))
    )
    (net (code "116") (name "unconnected-(U1-NC-Pad2)") (class "Default")
      (node (ref "U1") (pin "2") (pinfunction "NC_2") (pintype "bidirectional"))
    )
    (net (code "117") (name "unconnected-(U1-NC-Pad3)") (class "Default")
      (node (ref "U1") (pin "3") (pinfunction "NC_3") (pintype "bidirectional"))
    )
    (net (code "118") (name "unconnected-(U6-RS485{slash}IO2-Pad12)") (class "Default")
      (node (ref "U6") (pin "12") (pinfunction "RS485/IO2_12") (pintype "bidirectional"))
    )
    (net (code "119") (name "unconnected-(U6-SUSPEND-Pad17)") (class "Default")
      (node (ref "U6") (pin "17") (pinfunction "SUSPEND_17") (pintype "bidirectional"))
    )
    (net (code "120") (name "unconnected-(U6-WAKEUP{slash}IO3-Pad11)") (class "Default")
      (node (ref "U6") (pin "11") (pinfunction "WAKEUP/IO3_11") (pintype "bidirectional"))
    )
    (net (code "121") (name "unconnected-(U6-~{CTS}-Pad18)") (class "Default")
      (node (ref "U6") (pin "18") (pinfunction "~{CTS}_18") (pintype "bidirectional"))
    )
    (net (code "122") (name "unconnected-(U6-~{DCD}-Pad24)") (class "Default")
      (node (ref "U6") (pin "24") (pinfunction "~{DCD}_24") (pintype "bidirectional"))
    )
    (net (code "123") (name "unconnected-(U6-~{DSR}-Pad22)") (class "Default")
      (node (ref "U6") (pin "22") (pinfunction "~{DSR}_22") (pintype "bidirectional"))
    )
    (net (code "124") (name "unconnected-(U6-~{RI}{slash}CLK-Pad1)") (class "Default")
      (node (ref "U6") (pin "1") (pinfunction "~{RI}/CLK_1") (pintype "bidirectional"))
    )
    (net (code "125") (name "unconnected-(U6-~{RTS}-Pad19)") (class "Default")
      (node (ref "U6") (pin "19") (pinfunction "~{RTS}_19") (pintype "bidirectional"))
    )
    (net (code "126") (name "unconnected-(U6-~{SUSPEND}-Pad15)") (class "Default")
      (node (ref "U6") (pin "15") (pinfunction "~{SUSPEND}_15") (pintype "bidirectional"))
    )
    (net (code "127") (name "unconnected-(U8-BS2-Pad12)") (class "Default")
      (node (ref "U8") (pin "12") (pinfunction "BS2_12") (pintype "input"))
    )
    (net (code "128") (name "unconnected-(U8-D3-Pad21)") (class "Default")
      (node (ref "U8") (pin "21") (pinfunction "D3_21") (pintype "input"))
    )
    (net (code "129") (name "unconnected-(U8-D4-Pad22)") (class "Default")
      (node (ref "U8") (pin "22") (pinfunction "D4_22") (pintype "input"))
    )
    (net (code "130") (name "unconnected-(U8-D5-Pad23)") (class "Default")
      (node (ref "U8") (pin "23") (pinfunction "D5_23") (pintype "input"))
    )
    (net (code "131") (name "unconnected-(U8-D6-Pad24)") (class "Default")
      (node (ref "U8") (pin "24") (pinfunction "D6_24") (pintype "input"))
    )
    (net (code "132") (name "unconnected-(U8-D7-Pad25)") (class "Default")
      (node (ref "U8") (pin "25") (pinfunction "D7_25") (pintype "input"))
    )
    (net (code "133") (name "unconnected-(U8-E{slash}RD-Pad17)") (class "Default")
      (node (ref "U8") (pin "17") (pinfunction "E/RD_17") (pintype "input"))
    )
    (net (code "134") (name "unconnected-(U8-NC-Pad7)") (class "Default")
      (node (ref "U8") (pin "7") (pinfunction "NC_7") (pintype "no_connect"))
    )
    (net (code "135") (name "unconnected-(U8-R{slash}W-Pad16)") (class "Default")
      (node (ref "U8") (pin "16") (pinfunction "R/W_16") (pintype "input"))
    )
    (net (code "136") (name "unconnected-(U11-NC-Pad3)") (class "Default")
      (node (ref "U11") (pin "3") (pinfunction "NC_3") (pintype "bidirectional"))
    )
  )
)
